# ETH_PHY_SW_L2L3.net
KiCad netlist of a schematic drawn in Altium Designer
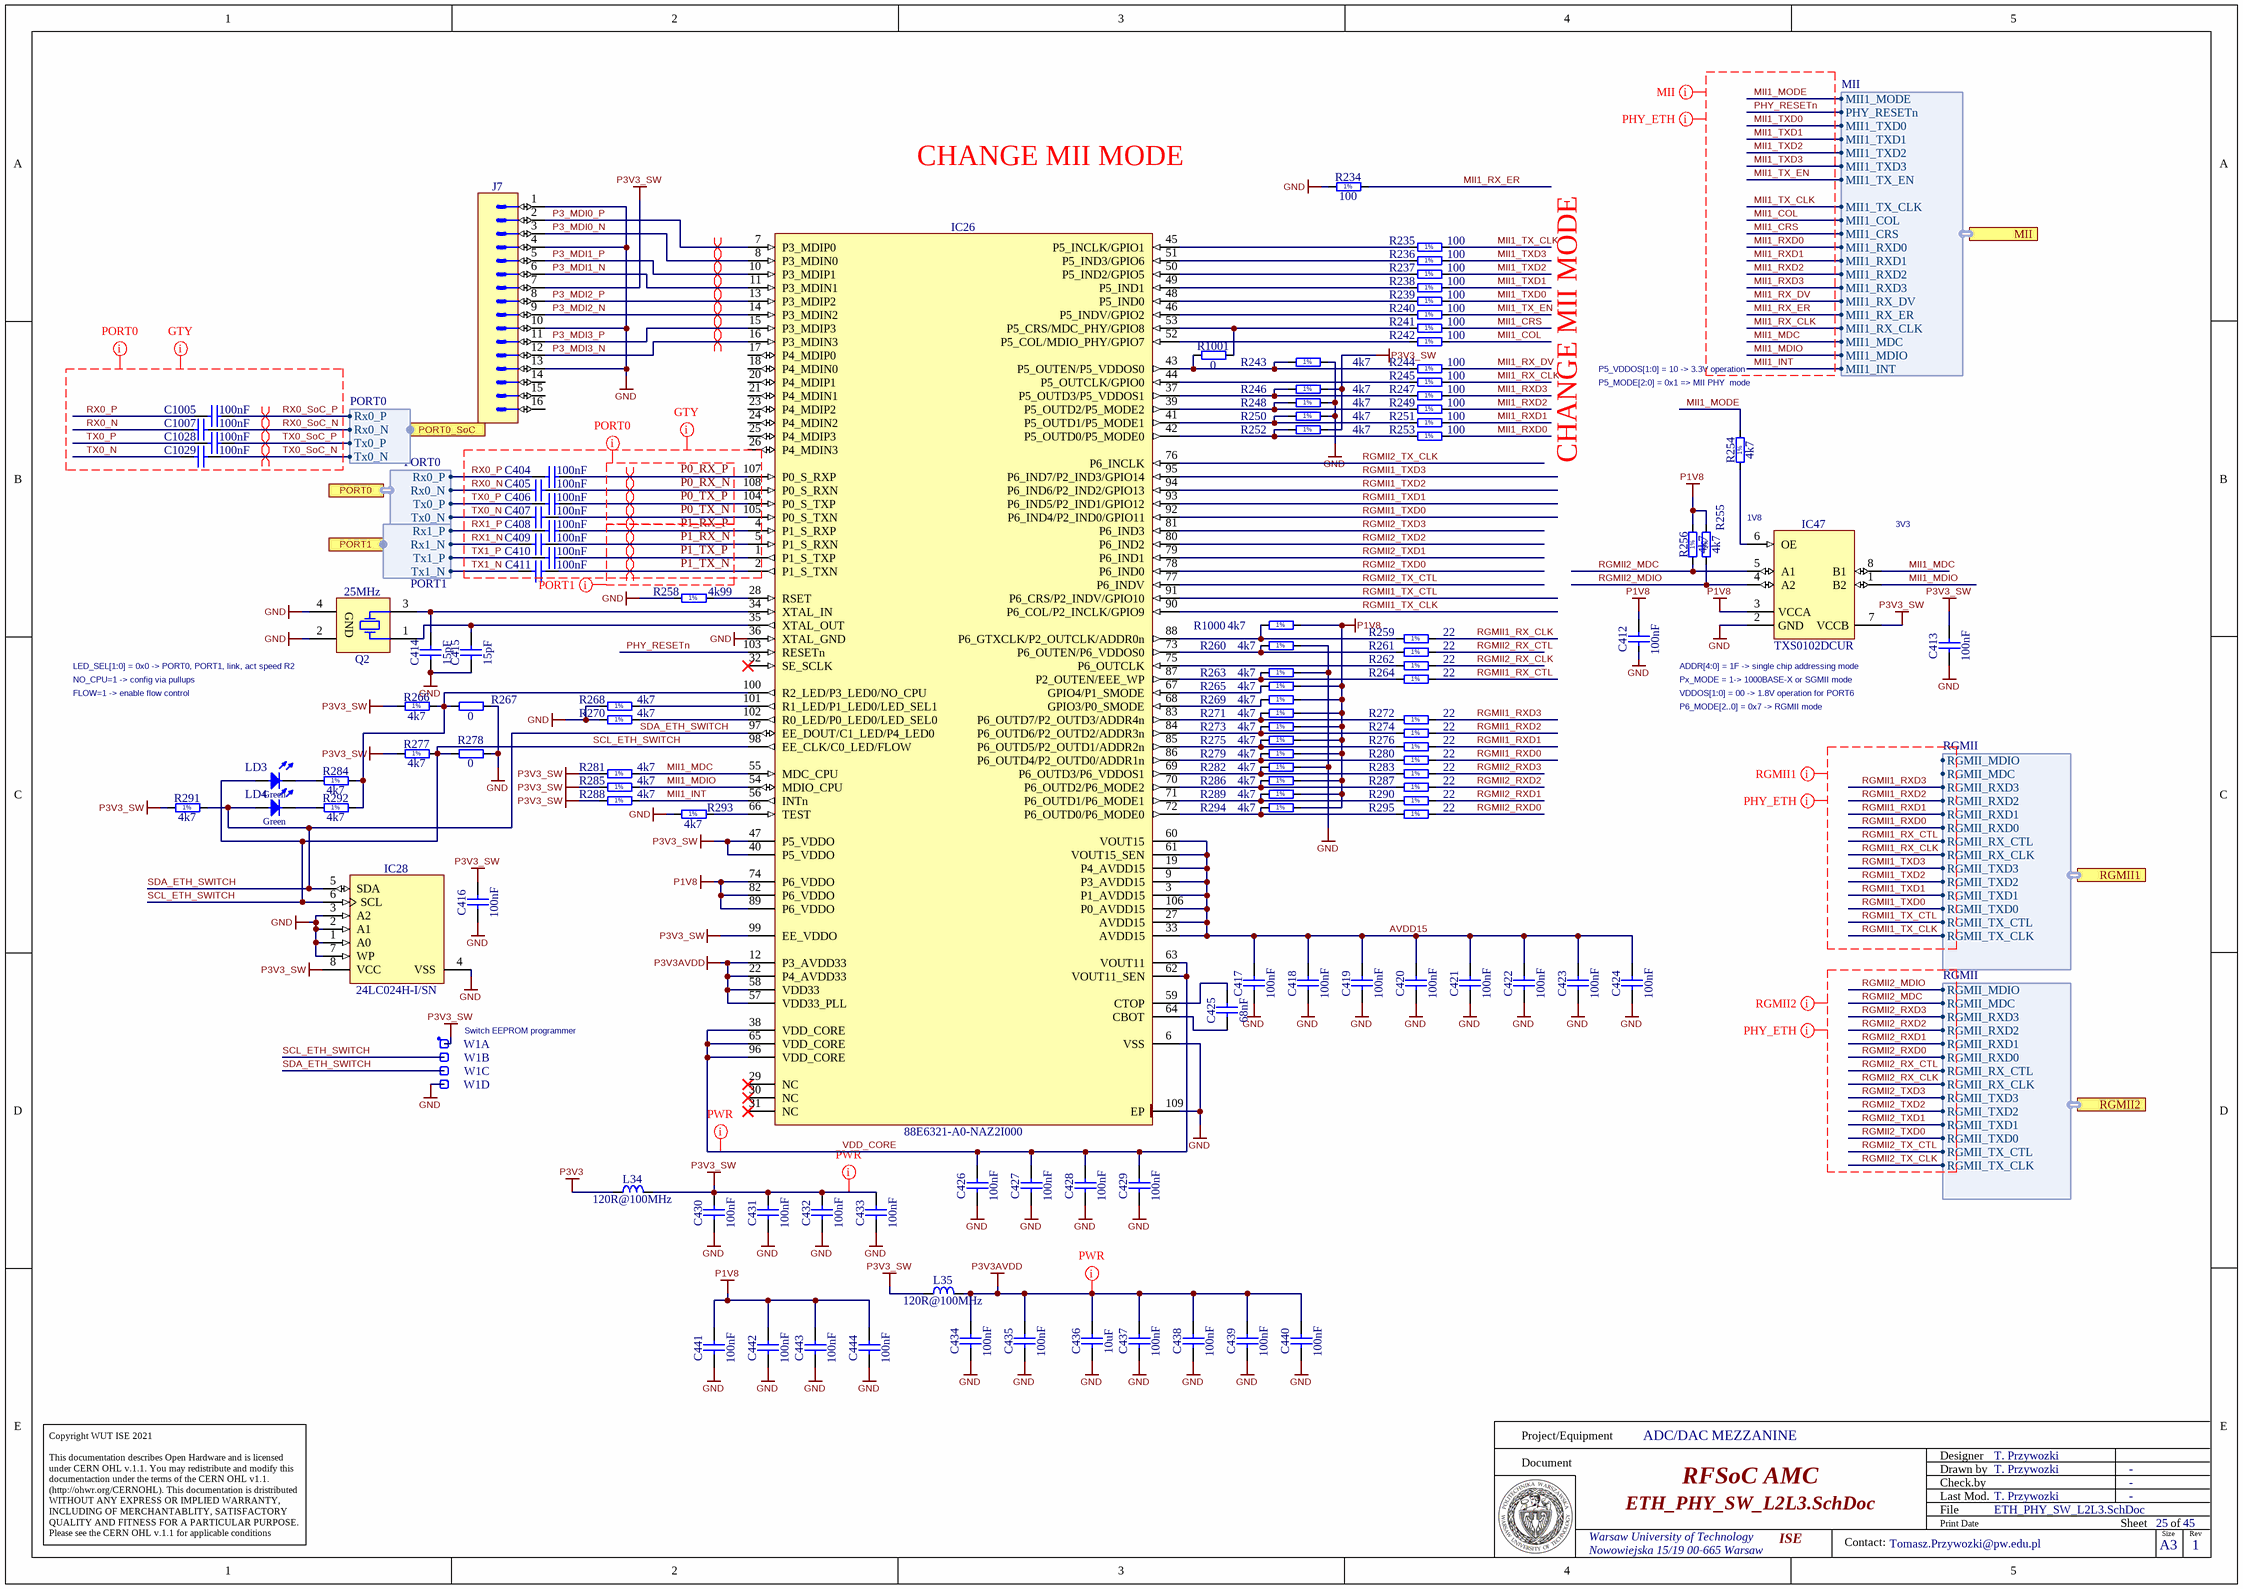
[diagram p0: ETH_PHY_SW_L2L3.SchDoc]

(export (version "E")
  (design (tool "Eeschema 10.0.6"))
  (components
    (comp (ref "C404")
      (value "100nF")
      (footprint "CAPC0603X33N")
      (description "Non-polarised capacitor")
      (fields
        (field (name "MANUFACTURER PART NUMBER") "CC0201_100NF_6.3V_10%_X5R")
        (field (name "MANUFACTURER") "GENERIC")
        (field (name "AUTHOR") "CERN DEM JLC")
      )
      (libsource (lib "Capacitors") (part "Capacitor - non polarized"))
    )
    (comp (ref "C405")
      (value "100nF")
      (footprint "CAPC0603X33N")
      (description "Non-polarised capacitor")
      (fields
        (field (name "MANUFACTURER PART NUMBER") "CC0201_100NF_6.3V_10%_X5R")
        (field (name "MANUFACTURER") "GENERIC")
        (field (name "AUTHOR") "CERN DEM JLC")
      )
      (libsource (lib "Capacitors") (part "Capacitor - non polarized"))
    )
    (comp (ref "C406")
      (value "100nF")
      (footprint "CAPC0603X33N")
      (description "Non-polarised capacitor")
      (fields
        (field (name "MANUFACTURER PART NUMBER") "CC0201_100NF_6.3V_10%_X5R")
        (field (name "MANUFACTURER") "GENERIC")
        (field (name "AUTHOR") "CERN DEM JLC")
      )
      (libsource (lib "Capacitors") (part "Capacitor - non polarized"))
    )
    (comp (ref "C407")
      (value "100nF")
      (footprint "CAPC0603X33N")
      (description "Non-polarised capacitor")
      (fields
        (field (name "MANUFACTURER PART NUMBER") "CC0201_100NF_6.3V_10%_X5R")
        (field (name "MANUFACTURER") "GENERIC")
        (field (name "AUTHOR") "CERN DEM JLC")
      )
      (libsource (lib "Capacitors") (part "Capacitor - non polarized"))
    )
    (comp (ref "C408")
      (value "100nF")
      (footprint "CAPC0603X33N")
      (description "Non-polarised capacitor")
      (fields
        (field (name "MANUFACTURER PART NUMBER") "CC0201_100NF_6.3V_10%_X5R")
        (field (name "MANUFACTURER") "GENERIC")
        (field (name "AUTHOR") "CERN DEM JLC")
      )
      (libsource (lib "Capacitors") (part "Capacitor - non polarized"))
    )
    (comp (ref "C409")
      (value "100nF")
      (footprint "CAPC0603X33N")
      (description "Non-polarised capacitor")
      (fields
        (field (name "MANUFACTURER PART NUMBER") "CC0201_100NF_6.3V_10%_X5R")
        (field (name "MANUFACTURER") "GENERIC")
        (field (name "AUTHOR") "CERN DEM JLC")
      )
      (libsource (lib "Capacitors") (part "Capacitor - non polarized"))
    )
    (comp (ref "C410")
      (value "100nF")
      (footprint "CAPC0603X33N")
      (description "Non-polarised capacitor")
      (fields
        (field (name "MANUFACTURER PART NUMBER") "CC0201_100NF_6.3V_10%_X5R")
        (field (name "MANUFACTURER") "GENERIC")
        (field (name "AUTHOR") "CERN DEM JLC")
      )
      (libsource (lib "Capacitors") (part "Capacitor - non polarized"))
    )
    (comp (ref "C411")
      (value "100nF")
      (footprint "CAPC0603X33N")
      (description "Non-polarised capacitor")
      (fields
        (field (name "MANUFACTURER PART NUMBER") "CC0201_100NF_6.3V_10%_X5R")
        (field (name "MANUFACTURER") "GENERIC")
        (field (name "AUTHOR") "CERN DEM JLC")
      )
      (libsource (lib "Capacitors") (part "Capacitor - non polarized"))
    )
    (comp (ref "C412")
      (value "100nF")
      (footprint "CAPC0603X33N")
      (description "Non-polarised capacitor")
      (fields
        (field (name "MANUFACTURER PART NUMBER") "CC0201_100NF_6.3V_10%_X5R")
        (field (name "MANUFACTURER") "GENERIC")
        (field (name "AUTHOR") "CERN DEM JLC")
      )
      (libsource (lib "Capacitors") (part "Capacitor - non polarized"))
    )
    (comp (ref "C413")
      (value "100nF")
      (footprint "CAPC0603X33N")
      (description "Non-polarised capacitor")
      (fields
        (field (name "MANUFACTURER PART NUMBER") "CC0201_100NF_6.3V_10%_X5R")
        (field (name "MANUFACTURER") "GENERIC")
        (field (name "AUTHOR") "CERN DEM JLC")
      )
      (libsource (lib "Capacitors") (part "Capacitor - non polarized"))
    )
    (comp (ref "C414")
      (value "15pF")
      (footprint "CAPC1005X55N")
      (description "Non-polarised capacitor")
      (fields
        (field (name "MANUFACTURER PART NUMBER") "CC0402_15PF_50V_5%_C0G")
        (field (name "MANUFACTURER") "GENERIC")
        (field (name "AUTHOR") "CERN DEM JLC")
      )
      (libsource (lib "Capacitors") (part "Capacitor - non polarized"))
    )
    (comp (ref "C415")
      (value "15pF")
      (footprint "CAPC1005X55N")
      (description "Non-polarised capacitor")
      (fields
        (field (name "MANUFACTURER PART NUMBER") "CC0402_15PF_50V_5%_C0G")
        (field (name "MANUFACTURER") "GENERIC")
        (field (name "AUTHOR") "CERN DEM JLC")
      )
      (libsource (lib "Capacitors") (part "Capacitor - non polarized"))
    )
    (comp (ref "C416")
      (value "100nF")
      (footprint "CAPC0603X33N")
      (description "Non-polarised capacitor")
      (fields
        (field (name "MANUFACTURER PART NUMBER") "CC0201_100NF_6.3V_10%_X5R")
        (field (name "MANUFACTURER") "GENERIC")
        (field (name "AUTHOR") "CERN DEM JLC")
      )
      (libsource (lib "Capacitors") (part "Capacitor - non polarized"))
    )
    (comp (ref "C417")
      (value "100nF")
      (footprint "CAPC0603X33N")
      (description "Non-polarised capacitor")
      (fields
        (field (name "MANUFACTURER PART NUMBER") "CC0201_100NF_6.3V_10%_X5R")
        (field (name "MANUFACTURER") "GENERIC")
        (field (name "AUTHOR") "CERN DEM JLC")
      )
      (libsource (lib "Capacitors") (part "Capacitor - non polarized"))
    )
    (comp (ref "C418")
      (value "100nF")
      (footprint "CAPC0603X33N")
      (description "Non-polarised capacitor")
      (fields
        (field (name "MANUFACTURER PART NUMBER") "CC0201_100NF_6.3V_10%_X5R")
        (field (name "MANUFACTURER") "GENERIC")
        (field (name "AUTHOR") "CERN DEM JLC")
      )
      (libsource (lib "Capacitors") (part "Capacitor - non polarized"))
    )
    (comp (ref "C419")
      (value "100nF")
      (footprint "CAPC0603X33N")
      (description "Non-polarised capacitor")
      (fields
        (field (name "MANUFACTURER PART NUMBER") "CC0201_100NF_6.3V_10%_X5R")
        (field (name "MANUFACTURER") "GENERIC")
        (field (name "AUTHOR") "CERN DEM JLC")
      )
      (libsource (lib "Capacitors") (part "Capacitor - non polarized"))
    )
    (comp (ref "C420")
      (value "100nF")
      (footprint "CAPC0603X33N")
      (description "Non-polarised capacitor")
      (fields
        (field (name "MANUFACTURER PART NUMBER") "CC0201_100NF_6.3V_10%_X5R")
        (field (name "MANUFACTURER") "GENERIC")
        (field (name "AUTHOR") "CERN DEM JLC")
      )
      (libsource (lib "Capacitors") (part "Capacitor - non polarized"))
    )
    (comp (ref "C421")
      (value "100nF")
      (footprint "CAPC0603X33N")
      (description "Non-polarised capacitor")
      (fields
        (field (name "MANUFACTURER PART NUMBER") "CC0201_100NF_6.3V_10%_X5R")
        (field (name "MANUFACTURER") "GENERIC")
        (field (name "AUTHOR") "CERN DEM JLC")
      )
      (libsource (lib "Capacitors") (part "Capacitor - non polarized"))
    )
    (comp (ref "C422")
      (value "100nF")
      (footprint "CAPC0603X33N")
      (description "Non-polarised capacitor")
      (fields
        (field (name "MANUFACTURER PART NUMBER") "CC0201_100NF_6.3V_10%_X5R")
        (field (name "MANUFACTURER") "GENERIC")
        (field (name "AUTHOR") "CERN DEM JLC")
      )
      (libsource (lib "Capacitors") (part "Capacitor - non polarized"))
    )
    (comp (ref "C423")
      (value "100nF")
      (footprint "CAPC0603X33N")
      (description "Non-polarised capacitor")
      (fields
        (field (name "MANUFACTURER PART NUMBER") "CC0201_100NF_6.3V_10%_X5R")
        (field (name "MANUFACTURER") "GENERIC")
        (field (name "AUTHOR") "CERN DEM JLC")
      )
      (libsource (lib "Capacitors") (part "Capacitor - non polarized"))
    )
    (comp (ref "C424")
      (value "100nF")
      (footprint "CAPC0603X33N")
      (description "Non-polarised capacitor")
      (fields
        (field (name "MANUFACTURER PART NUMBER") "CC0201_100NF_6.3V_10%_X5R")
        (field (name "MANUFACTURER") "GENERIC")
        (field (name "AUTHOR") "CERN DEM JLC")
      )
      (libsource (lib "Capacitors") (part "Capacitor - non polarized"))
    )
    (comp (ref "C425")
      (value "68nF")
      (footprint "CAPC1005X55N")
      (description "Non-polarised capacitor")
      (fields
        (field (name "MANUFACTURER PART NUMBER") "CC0402_68NF_16V_10%_X7R")
        (field (name "MANUFACTURER") "GENERIC")
        (field (name "AUTHOR") "CERN DEM JLC")
      )
      (libsource (lib "Capacitors") (part "Capacitor - non polarized"))
    )
    (comp (ref "C426")
      (value "100nF")
      (footprint "CAPC0603X33N")
      (description "Non-polarised capacitor")
      (fields
        (field (name "MANUFACTURER PART NUMBER") "CC0201_100NF_6.3V_10%_X5R")
        (field (name "MANUFACTURER") "GENERIC")
        (field (name "AUTHOR") "CERN DEM JLC")
      )
      (libsource (lib "Capacitors") (part "Capacitor - non polarized"))
    )
    (comp (ref "C427")
      (value "100nF")
      (footprint "CAPC0603X33N")
      (description "Non-polarised capacitor")
      (fields
        (field (name "MANUFACTURER PART NUMBER") "CC0201_100NF_6.3V_10%_X5R")
        (field (name "MANUFACTURER") "GENERIC")
        (field (name "AUTHOR") "CERN DEM JLC")
      )
      (libsource (lib "Capacitors") (part "Capacitor - non polarized"))
    )
    (comp (ref "C428")
      (value "100nF")
      (footprint "CAPC0603X33N")
      (description "Non-polarised capacitor")
      (fields
        (field (name "MANUFACTURER PART NUMBER") "CC0201_100NF_6.3V_10%_X5R")
        (field (name "MANUFACTURER") "GENERIC")
        (field (name "AUTHOR") "CERN DEM JLC")
      )
      (libsource (lib "Capacitors") (part "Capacitor - non polarized"))
    )
    (comp (ref "C429")
      (value "100nF")
      (footprint "CAPC0603X33N")
      (description "Non-polarised capacitor")
      (fields
        (field (name "MANUFACTURER PART NUMBER") "CC0201_100NF_6.3V_10%_X5R")
        (field (name "MANUFACTURER") "GENERIC")
        (field (name "AUTHOR") "CERN DEM JLC")
      )
      (libsource (lib "Capacitors") (part "Capacitor - non polarized"))
    )
    (comp (ref "C430")
      (value "100nF")
      (footprint "CAPC0603X33N")
      (description "Non-polarised capacitor")
      (fields
        (field (name "MANUFACTURER PART NUMBER") "CC0201_100NF_6.3V_10%_X5R")
        (field (name "MANUFACTURER") "GENERIC")
        (field (name "AUTHOR") "CERN DEM JLC")
      )
      (libsource (lib "Capacitors") (part "Capacitor - non polarized"))
    )
    (comp (ref "C431")
      (value "100nF")
      (footprint "CAPC0603X33N")
      (description "Non-polarised capacitor")
      (fields
        (field (name "MANUFACTURER PART NUMBER") "CC0201_100NF_6.3V_10%_X5R")
        (field (name "MANUFACTURER") "GENERIC")
        (field (name "AUTHOR") "CERN DEM JLC")
      )
      (libsource (lib "Capacitors") (part "Capacitor - non polarized"))
    )
    (comp (ref "C432")
      (value "100nF")
      (footprint "CAPC0603X33N")
      (description "Non-polarised capacitor")
      (fields
        (field (name "MANUFACTURER PART NUMBER") "CC0201_100NF_6.3V_10%_X5R")
        (field (name "MANUFACTURER") "GENERIC")
        (field (name "AUTHOR") "CERN DEM JLC")
      )
      (libsource (lib "Capacitors") (part "Capacitor - non polarized"))
    )
    (comp (ref "C433")
      (value "100nF")
      (footprint "CAPC0603X33N")
      (description "Non-polarised capacitor")
      (fields
        (field (name "MANUFACTURER PART NUMBER") "CC0201_100NF_6.3V_10%_X5R")
        (field (name "MANUFACTURER") "GENERIC")
        (field (name "AUTHOR") "CERN DEM JLC")
      )
      (libsource (lib "Capacitors") (part "Capacitor - non polarized"))
    )
    (comp (ref "C434")
      (value "100nF")
      (footprint "CAPC0603X33N")
      (description "Non-polarised capacitor")
      (fields
        (field (name "MANUFACTURER PART NUMBER") "CC0201_100NF_6.3V_10%_X5R")
        (field (name "MANUFACTURER") "GENERIC")
        (field (name "AUTHOR") "CERN DEM JLC")
      )
      (libsource (lib "Capacitors") (part "Capacitor - non polarized"))
    )
    (comp (ref "C435")
      (value "100nF")
      (footprint "CAPC0603X33N")
      (description "Non-polarised capacitor")
      (fields
        (field (name "MANUFACTURER PART NUMBER") "CC0201_100NF_6.3V_10%_X5R")
        (field (name "MANUFACTURER") "GENERIC")
        (field (name "AUTHOR") "CERN DEM JLC")
      )
      (libsource (lib "Capacitors") (part "Capacitor - non polarized"))
    )
    (comp (ref "C436")
      (value "10uF")
      (footprint "CAPC1608X87N")
      (description "Non-polarised capacitor")
      (fields
        (field (name "MANUFACTURER PART NUMBER") "CC0603_10uF_6.3V_20%_X5R")
        (field (name "MANUFACTURER") "GENERIC")
        (field (name "AUTHOR") "CERN DEM JLC")
      )
      (libsource (lib "Capacitors") (part "Capacitor - non polarized"))
    )
    (comp (ref "C437")
      (value "100nF")
      (footprint "CAPC0603X33N")
      (description "Non-polarised capacitor")
      (fields
        (field (name "MANUFACTURER PART NUMBER") "CC0201_100NF_6.3V_10%_X5R")
        (field (name "MANUFACTURER") "GENERIC")
        (field (name "AUTHOR") "CERN DEM JLC")
      )
      (libsource (lib "Capacitors") (part "Capacitor - non polarized"))
    )
    (comp (ref "C438")
      (value "100nF")
      (footprint "CAPC0603X33N")
      (description "Non-polarised capacitor")
      (fields
        (field (name "MANUFACTURER PART NUMBER") "CC0201_100NF_6.3V_10%_X5R")
        (field (name "MANUFACTURER") "GENERIC")
        (field (name "AUTHOR") "CERN DEM JLC")
      )
      (libsource (lib "Capacitors") (part "Capacitor - non polarized"))
    )
    (comp (ref "C439")
      (value "100nF")
      (footprint "CAPC0603X33N")
      (description "Non-polarised capacitor")
      (fields
        (field (name "MANUFACTURER PART NUMBER") "CC0201_100NF_6.3V_10%_X5R")
        (field (name "MANUFACTURER") "GENERIC")
        (field (name "AUTHOR") "CERN DEM JLC")
      )
      (libsource (lib "Capacitors") (part "Capacitor - non polarized"))
    )
    (comp (ref "C440")
      (value "100nF")
      (footprint "CAPC0603X33N")
      (description "Non-polarised capacitor")
      (fields
        (field (name "MANUFACTURER PART NUMBER") "CC0201_100NF_6.3V_10%_X5R")
        (field (name "MANUFACTURER") "GENERIC")
        (field (name "AUTHOR") "CERN DEM JLC")
      )
      (libsource (lib "Capacitors") (part "Capacitor - non polarized"))
    )
    (comp (ref "C441")
      (value "100nF")
      (footprint "CAPC0603X33N")
      (description "Non-polarised capacitor")
      (fields
        (field (name "MANUFACTURER PART NUMBER") "CC0201_100NF_6.3V_10%_X5R")
        (field (name "MANUFACTURER") "GENERIC")
        (field (name "AUTHOR") "CERN DEM JLC")
      )
      (libsource (lib "Capacitors") (part "Capacitor - non polarized"))
    )
    (comp (ref "C442")
      (value "100nF")
      (footprint "CAPC0603X33N")
      (description "Non-polarised capacitor")
      (fields
        (field (name "MANUFACTURER PART NUMBER") "CC0201_100NF_6.3V_10%_X5R")
        (field (name "MANUFACTURER") "GENERIC")
        (field (name "AUTHOR") "CERN DEM JLC")
      )
      (libsource (lib "Capacitors") (part "Capacitor - non polarized"))
    )
    (comp (ref "C443")
      (value "100nF")
      (footprint "CAPC0603X33N")
      (description "Non-polarised capacitor")
      (fields
        (field (name "MANUFACTURER PART NUMBER") "CC0201_100NF_6.3V_10%_X5R")
        (field (name "MANUFACTURER") "GENERIC")
        (field (name "AUTHOR") "CERN DEM JLC")
      )
      (libsource (lib "Capacitors") (part "Capacitor - non polarized"))
    )
    (comp (ref "C444")
      (value "100nF")
      (footprint "CAPC0603X33N")
      (description "Non-polarised capacitor")
      (fields
        (field (name "MANUFACTURER PART NUMBER") "CC0201_100NF_6.3V_10%_X5R")
        (field (name "MANUFACTURER") "GENERIC")
        (field (name "AUTHOR") "CERN DEM JLC")
      )
      (libsource (lib "Capacitors") (part "Capacitor - non polarized"))
    )
    (comp (ref "C1005")
      (value "100nF")
      (footprint "CAPC0603X33N")
      (description "Non-polarised capacitor")
      (fields
        (field (name "MANUFACTURER PART NUMBER") "CC0201_100NF_6.3V_10%_X5R")
        (field (name "MANUFACTURER") "GENERIC")
        (field (name "AUTHOR") "CERN DEM JLC")
      )
      (libsource (lib "Capacitors") (part "Capacitor - non polarized"))
    )
    (comp (ref "C1007")
      (value "100nF")
      (footprint "CAPC0603X33N")
      (description "Non-polarised capacitor")
      (fields
        (field (name "MANUFACTURER PART NUMBER") "CC0201_100NF_6.3V_10%_X5R")
        (field (name "MANUFACTURER") "GENERIC")
        (field (name "AUTHOR") "CERN DEM JLC")
      )
      (libsource (lib "Capacitors") (part "Capacitor - non polarized"))
    )
    (comp (ref "C1028")
      (value "100nF")
      (footprint "CAPC0603X33N")
      (description "Non-polarised capacitor")
      (fields
        (field (name "MANUFACTURER PART NUMBER") "CC0201_100NF_6.3V_10%_X5R")
        (field (name "MANUFACTURER") "GENERIC")
        (field (name "AUTHOR") "CERN DEM JLC")
      )
      (libsource (lib "Capacitors") (part "Capacitor - non polarized"))
    )
    (comp (ref "C1029")
      (value "100nF")
      (footprint "CAPC0603X33N")
      (description "Non-polarised capacitor")
      (fields
        (field (name "MANUFACTURER PART NUMBER") "CC0201_100NF_6.3V_10%_X5R")
        (field (name "MANUFACTURER") "GENERIC")
        (field (name "AUTHOR") "CERN DEM JLC")
      )
      (libsource (lib "Capacitors") (part "Capacitor - non polarized"))
    )
    (comp (ref "IC26")
      (value "88E6321-A0-NAZ2I000")
      (footprint "QFN40P1200X1200X90-109N-S475")
      (description "7 Port Gigabit AVB Switch With 2 PHYs And Energy Efficient Ethernet (EEE)")
      (fields (field (name "MANUFACTURER") "MARVELL") (field (name "AUTHOR") "CERN DEM MR"))
      (libsource (lib "ICs And Semiconductors") (part "88E6321-A0-NAZ"))
    )
    (comp (ref "IC28")
      (value "24LC024H-I/SN")
      (footprint "SOIC127P600X175-8N")
      (description "2K I2C Serial EEPROM With Half-Array Write Protect")
      (fields (field (name "MANUFACTURER") "MICROCHIP TECHNOLOGY") (field (name "AUTHOR") "CERN DEM JLC"))
      (libsource (lib "ICs And Semiconductors") (part "24LC024H-I/SN"))
    )
    (comp (ref "IC47")
      (value "TXS0102DCUR")
      (footprint "SOP50P310X90-8N")
      (description "2-Bit Bidirectionnal Voltage-Level Translator for Open-Drain And Push-Pull Applications")
      (fields (field (name "MANUFACTURER") "TEXAS INSTRUMENTS") (field (name "AUTHOR") "CERN DEM JLC"))
      (libsource (lib "ICs And Semiconductors") (part "TXS0102DCU"))
    )
    (comp (ref "J7")
      (value "Milli-Grid™")
      (footprint "MOLEX_87759-1650")
      (description "Connector 16 Male")
      (fields
        (field (name "PART NUMBER") "MOLEX_87759-1650")
        (field (name "MANUFACTURER") "MOLEX")
        (field (name "AUTHOR") "CERN DEM MR")
      )
      (libsource (lib "Connectors") (part "Connector 16 Male"))
    )
    (comp (ref "L34")
      (value "120R@100MHz")
      (footprint "INDC1608X65N")
      (description "Inductor")
      (fields
        (field (name "MANUFACTURER PART NUMBER") "BLM18SG121TN1D")
        (field (name "MANUFACTURER") "MURATA")
        (field (name "AUTHOR") "CERN DEM JLC")
      )
      (libsource (lib "Inductors & Transformers") (part "Inductor"))
    )
    (comp (ref "L35")
      (value "120R@100MHz")
      (footprint "INDC1608X65N")
      (description "Inductor")
      (fields
        (field (name "MANUFACTURER PART NUMBER") "BLM18SG121TN1D")
        (field (name "MANUFACTURER") "MURATA")
        (field (name "AUTHOR") "CERN DEM JLC")
      )
      (libsource (lib "Inductors & Transformers") (part "Inductor"))
    )
    (comp (ref "LD3")
      (value "Green")
      (footprint "LED_KINGBRIGHT_KPH-1608CGCK")
      (description "LED Green 1C 2A")
      (fields
        (field (name "MANUFACTURER PART NUMBER") "KPH-1608CGCK")
        (field (name "MANUFACTURER") "KINGBRIGHT")
        (field (name "AUTHOR") "CERN DEM JLC")
      )
      (libsource (lib "ICs And Semiconductors") (part "LED Green 1C 2A"))
    )
    (comp (ref "LD4")
      (value "Green")
      (footprint "LED_KINGBRIGHT_KPH-1608CGCK")
      (description "LED Green 1C 2A")
      (fields
        (field (name "MANUFACTURER PART NUMBER") "KPH-1608CGCK")
        (field (name "MANUFACTURER") "KINGBRIGHT")
        (field (name "AUTHOR") "CERN DEM JLC")
      )
      (libsource (lib "ICs And Semiconductors") (part "LED Green 1C 2A"))
    )
    (comp (ref "Q2")
      (value "25MHz")
      (footprint "XTAL_TXC_8Y")
      (description "Crystal 4 pins 1=XTAL Control 2=GND3=XTAL 4=GND")
      (fields
        (field (name "MANUFACTURER PART NUMBER") "8Y-25.000MAAJ-T")
        (field (name "MANUFACTURER") "TXC CORPORATION")
        (field (name "AUTHOR") "CERN DEM JLC")
      )
      (libsource (lib "ICs And Semiconductors") (part "Quartz Crystal 1X 2GND 3X 4GND"))
    )
    (comp (ref "R234")
      (value "100")
      (footprint "RESC0603X28N")
      (description "Resistor - 1%")
      (fields
        (field (name "MANUFACTURER PART NUMBER") "R0201_100R_1%_0.05W_200PPM")
        (field (name "MANUFACTURER") "GENERIC")
        (field (name "AUTHOR") "CERN DEM JLC")
      )
      (libsource (lib "Resistors") (part "Resistor - 1%"))
    )
    (comp (ref "R235")
      (value "100")
      (footprint "RESC0603X28N")
      (description "Resistor - 1%")
      (fields
        (field (name "MANUFACTURER PART NUMBER") "R0201_100R_1%_0.05W_200PPM")
        (field (name "MANUFACTURER") "GENERIC")
        (field (name "AUTHOR") "CERN DEM JLC")
      )
      (libsource (lib "Resistors") (part "Resistor - 1%"))
    )
    (comp (ref "R236")
      (value "100")
      (footprint "RESC0603X28N")
      (description "Resistor - 1%")
      (fields
        (field (name "MANUFACTURER PART NUMBER") "R0201_100R_1%_0.05W_200PPM")
        (field (name "MANUFACTURER") "GENERIC")
        (field (name "AUTHOR") "CERN DEM JLC")
      )
      (libsource (lib "Resistors") (part "Resistor - 1%"))
    )
    (comp (ref "R237")
      (value "100")
      (footprint "RESC0603X28N")
      (description "Resistor - 1%")
      (fields
        (field (name "MANUFACTURER PART NUMBER") "R0201_100R_1%_0.05W_200PPM")
        (field (name "MANUFACTURER") "GENERIC")
        (field (name "AUTHOR") "CERN DEM JLC")
      )
      (libsource (lib "Resistors") (part "Resistor - 1%"))
    )
    (comp (ref "R238")
      (value "100")
      (footprint "RESC0603X28N")
      (description "Resistor - 1%")
      (fields
        (field (name "MANUFACTURER PART NUMBER") "R0201_100R_1%_0.05W_200PPM")
        (field (name "MANUFACTURER") "GENERIC")
        (field (name "AUTHOR") "CERN DEM JLC")
      )
      (libsource (lib "Resistors") (part "Resistor - 1%"))
    )
    (comp (ref "R239")
      (value "100")
      (footprint "RESC0603X28N")
      (description "Resistor - 1%")
      (fields
        (field (name "MANUFACTURER PART NUMBER") "R0201_100R_1%_0.05W_200PPM")
        (field (name "MANUFACTURER") "GENERIC")
        (field (name "AUTHOR") "CERN DEM JLC")
      )
      (libsource (lib "Resistors") (part "Resistor - 1%"))
    )
    (comp (ref "R240")
      (value "100")
      (footprint "RESC0603X28N")
      (description "Resistor - 1%")
      (fields
        (field (name "MANUFACTURER PART NUMBER") "R0201_100R_1%_0.05W_200PPM")
        (field (name "MANUFACTURER") "GENERIC")
        (field (name "AUTHOR") "CERN DEM JLC")
      )
      (libsource (lib "Resistors") (part "Resistor - 1%"))
    )
    (comp (ref "R241")
      (value "100")
      (footprint "RESC0603X28N")
      (description "Resistor - 1%")
      (fields
        (field (name "MANUFACTURER PART NUMBER") "R0201_100R_1%_0.05W_200PPM")
        (field (name "MANUFACTURER") "GENERIC")
        (field (name "AUTHOR") "CERN DEM JLC")
      )
      (libsource (lib "Resistors") (part "Resistor - 1%"))
    )
    (comp (ref "R242")
      (value "100")
      (footprint "RESC0603X28N")
      (description "Resistor - 1%")
      (fields
        (field (name "MANUFACTURER PART NUMBER") "R0201_100R_1%_0.05W_200PPM")
        (field (name "MANUFACTURER") "GENERIC")
        (field (name "AUTHOR") "CERN DEM JLC")
      )
      (libsource (lib "Resistors") (part "Resistor - 1%"))
    )
    (comp (ref "R243")
      (value "4k7")
      (footprint "RESC1005X40N")
      (description "Resistor - 1%")
      (fields
        (field (name "MANUFACTURER PART NUMBER") "R0402_4K7_1%_0.0625W_100PPM")
        (field (name "MANUFACTURER") "GENERIC")
        (field (name "AUTHOR") "CERN DEM JLC")
      )
      (libsource (lib "Resistors") (part "Resistor - 1%"))
    )
    (comp (ref "R244")
      (value "100")
      (footprint "RESC0603X28N")
      (description "Resistor - 1%")
      (fields
        (field (name "MANUFACTURER PART NUMBER") "R0201_100R_1%_0.05W_200PPM")
        (field (name "MANUFACTURER") "GENERIC")
        (field (name "AUTHOR") "CERN DEM JLC")
      )
      (libsource (lib "Resistors") (part "Resistor - 1%"))
    )
    (comp (ref "R245")
      (value "100")
      (footprint "RESC0603X28N")
      (description "Resistor - 1%")
      (fields
        (field (name "MANUFACTURER PART NUMBER") "R0201_100R_1%_0.05W_200PPM")
        (field (name "MANUFACTURER") "GENERIC")
        (field (name "AUTHOR") "CERN DEM JLC")
      )
      (libsource (lib "Resistors") (part "Resistor - 1%"))
    )
    (comp (ref "R246")
      (value "4k7")
      (footprint "RESC1005X40N")
      (description "Resistor - 1%")
      (fields
        (field (name "MANUFACTURER PART NUMBER") "R0402_4K7_1%_0.0625W_100PPM")
        (field (name "MANUFACTURER") "GENERIC")
        (field (name "AUTHOR") "CERN DEM JLC")
      )
      (libsource (lib "Resistors") (part "Resistor - 1%"))
    )
    (comp (ref "R247")
      (value "100")
      (footprint "RESC0603X28N")
      (description "Resistor - 1%")
      (fields
        (field (name "MANUFACTURER PART NUMBER") "R0201_100R_1%_0.05W_200PPM")
        (field (name "MANUFACTURER") "GENERIC")
        (field (name "AUTHOR") "CERN DEM JLC")
      )
      (libsource (lib "Resistors") (part "Resistor - 1%"))
    )
    (comp (ref "R248")
      (value "4k7")
      (footprint "RESC1005X40N")
      (description "Resistor - 1%")
      (fields
        (field (name "MANUFACTURER PART NUMBER") "R0402_4K7_1%_0.0625W_100PPM")
        (field (name "MANUFACTURER") "GENERIC")
        (field (name "AUTHOR") "CERN DEM JLC")
      )
      (libsource (lib "Resistors") (part "Resistor - 1%"))
    )
    (comp (ref "R249")
      (value "100")
      (footprint "RESC0603X28N")
      (description "Resistor - 1%")
      (fields
        (field (name "MANUFACTURER PART NUMBER") "R0201_100R_1%_0.05W_200PPM")
        (field (name "MANUFACTURER") "GENERIC")
        (field (name "AUTHOR") "CERN DEM JLC")
      )
      (libsource (lib "Resistors") (part "Resistor - 1%"))
    )
    (comp (ref "R250")
      (value "4k7")
      (footprint "RESC1005X40N")
      (description "Resistor - 1%")
      (fields
        (field (name "MANUFACTURER PART NUMBER") "R0402_4K7_1%_0.0625W_100PPM")
        (field (name "MANUFACTURER") "GENERIC")
        (field (name "AUTHOR") "CERN DEM JLC")
      )
      (libsource (lib "Resistors") (part "Resistor - 1%"))
    )
    (comp (ref "R251")
      (value "100")
      (footprint "RESC0603X28N")
      (description "Resistor - 1%")
      (fields
        (field (name "MANUFACTURER PART NUMBER") "R0201_100R_1%_0.05W_200PPM")
        (field (name "MANUFACTURER") "GENERIC")
        (field (name "AUTHOR") "CERN DEM JLC")
      )
      (libsource (lib "Resistors") (part "Resistor - 1%"))
    )
    (comp (ref "R252")
      (value "4k7")
      (footprint "RESC1005X40N")
      (description "Resistor - 1%")
      (fields
        (field (name "MANUFACTURER PART NUMBER") "R0402_4K7_1%_0.0625W_100PPM")
        (field (name "MANUFACTURER") "GENERIC")
        (field (name "AUTHOR") "CERN DEM JLC")
      )
      (libsource (lib "Resistors") (part "Resistor - 1%"))
    )
    (comp (ref "R253")
      (value "100")
      (footprint "RESC0603X28N")
      (description "Resistor - 1%")
      (fields
        (field (name "MANUFACTURER PART NUMBER") "R0201_100R_1%_0.05W_200PPM")
        (field (name "MANUFACTURER") "GENERIC")
        (field (name "AUTHOR") "CERN DEM JLC")
      )
      (libsource (lib "Resistors") (part "Resistor - 1%"))
    )
    (comp (ref "R254")
      (value "4k7")
      (footprint "RESC1005X40N")
      (description "Resistor - 1%")
      (fields
        (field (name "MANUFACTURER PART NUMBER") "R0402_4K7_1%_0.0625W_100PPM")
        (field (name "MANUFACTURER") "GENERIC")
        (field (name "AUTHOR") "CERN DEM JLC")
      )
      (libsource (lib "Resistors") (part "Resistor - 1%"))
    )
    (comp (ref "R255")
      (value "4k7")
      (footprint "RESC1005X40N")
      (description "Resistor - 1%")
      (fields
        (field (name "MANUFACTURER PART NUMBER") "R0402_4K7_1%_0.0625W_100PPM")
        (field (name "MANUFACTURER") "GENERIC")
        (field (name "AUTHOR") "CERN DEM JLC")
      )
      (libsource (lib "Resistors") (part "Resistor - 1%"))
    )
    (comp (ref "R256")
      (value "4k7")
      (footprint "RESC1005X40N")
      (description "Resistor - 1%")
      (fields
        (field (name "MANUFACTURER PART NUMBER") "R0402_4K7_1%_0.0625W_100PPM")
        (field (name "MANUFACTURER") "GENERIC")
        (field (name "AUTHOR") "CERN DEM JLC")
      )
      (libsource (lib "Resistors") (part "Resistor - 1%"))
    )
    (comp (ref "R258")
      (value "4k99")
      (footprint "RESC1608X55N")
      (description "Resistor - 1%")
      (fields
        (field (name "MANUFACTURER PART NUMBER") "R0603_4K99_1%_0.063W_50PPM")
        (field (name "MANUFACTURER") "GENERIC")
        (field (name "AUTHOR") "CERN DEM JLC")
      )
      (libsource (lib "Resistors") (part "Resistor - 1%"))
    )
    (comp (ref "R259")
      (value "22")
      (footprint "RESC1005X40N")
      (description "Resistor - 1%")
      (fields
        (field (name "MANUFACTURER PART NUMBER") "R0402_22R_1%_0.0625W_100PPM")
        (field (name "MANUFACTURER") "GENERIC")
        (field (name "AUTHOR") "CERN DEM JLC")
      )
      (libsource (lib "Resistors") (part "Resistor - 1%"))
    )
    (comp (ref "R260")
      (value "4k7")
      (footprint "RESC1005X40N")
      (description "Resistor - 1%")
      (fields
        (field (name "MANUFACTURER PART NUMBER") "R0402_4K7_1%_0.0625W_100PPM")
        (field (name "MANUFACTURER") "GENERIC")
        (field (name "AUTHOR") "CERN DEM JLC")
      )
      (libsource (lib "Resistors") (part "Resistor - 1%"))
    )
    (comp (ref "R261")
      (value "22")
      (footprint "RESC1005X40N")
      (description "Resistor - 1%")
      (fields
        (field (name "MANUFACTURER PART NUMBER") "R0402_22R_1%_0.0625W_100PPM")
        (field (name "MANUFACTURER") "GENERIC")
        (field (name "AUTHOR") "CERN DEM JLC")
      )
      (libsource (lib "Resistors") (part "Resistor - 1%"))
    )
    (comp (ref "R262")
      (value "22")
      (footprint "RESC1005X40N")
      (description "Resistor - 1%")
      (fields
        (field (name "MANUFACTURER PART NUMBER") "R0402_22R_1%_0.0625W_100PPM")
        (field (name "MANUFACTURER") "GENERIC")
        (field (name "AUTHOR") "CERN DEM JLC")
      )
      (libsource (lib "Resistors") (part "Resistor - 1%"))
    )
    (comp (ref "R263")
      (value "4k7")
      (footprint "RESC1005X40N")
      (description "Resistor - 1%")
      (fields
        (field (name "MANUFACTURER PART NUMBER") "R0402_4K7_1%_0.0625W_100PPM")
        (field (name "MANUFACTURER") "GENERIC")
        (field (name "AUTHOR") "CERN DEM JLC")
      )
      (libsource (lib "Resistors") (part "Resistor - 1%"))
    )
    (comp (ref "R264")
      (value "22")
      (footprint "RESC1005X40N")
      (description "Resistor - 1%")
      (fields
        (field (name "MANUFACTURER PART NUMBER") "R0402_22R_1%_0.0625W_100PPM")
        (field (name "MANUFACTURER") "GENERIC")
        (field (name "AUTHOR") "CERN DEM JLC")
      )
      (libsource (lib "Resistors") (part "Resistor - 1%"))
    )
    (comp (ref "R265")
      (value "4k7")
      (footprint "RESC1005X40N")
      (description "Resistor - 1%")
      (fields
        (field (name "MANUFACTURER PART NUMBER") "R0402_4K7_1%_0.0625W_100PPM")
        (field (name "MANUFACTURER") "GENERIC")
        (field (name "AUTHOR") "CERN DEM JLC")
      )
      (libsource (lib "Resistors") (part "Resistor - 1%"))
    )
    (comp (ref "R266")
      (value "4k7")
      (footprint "RESC1005X40N")
      (description "Resistor - 1%")
      (fields
        (field (name "MANUFACTURER PART NUMBER") "R0402_4K7_1%_0.0625W_100PPM")
        (field (name "MANUFACTURER") "GENERIC")
        (field (name "AUTHOR") "CERN DEM JLC")
      )
      (libsource (lib "Resistors") (part "Resistor - 1%"))
    )
    (comp (ref "R267")
      (value "0")
      (footprint "RESC1005X40N")
      (description "Resistor")
      (fields
        (field (name "PART NUMBER") "R0402_0R_JUMPER")
        (field (name "MANUFACTURER") "GENERIC")
        (field (name "AUTHOR") "CERN DEM JLC")
      )
      (libsource (lib "Resistors") (part "Resistor"))
    )
    (comp (ref "R268")
      (value "4k7")
      (footprint "RESC1005X40N")
      (description "Resistor - 1%")
      (fields
        (field (name "MANUFACTURER PART NUMBER") "R0402_4K7_1%_0.0625W_100PPM")
        (field (name "MANUFACTURER") "GENERIC")
        (field (name "AUTHOR") "CERN DEM JLC")
      )
      (libsource (lib "Resistors") (part "Resistor - 1%"))
    )
    (comp (ref "R269")
      (value "4k7")
      (footprint "RESC1005X40N")
      (description "Resistor - 1%")
      (fields
        (field (name "MANUFACTURER PART NUMBER") "R0402_4K7_1%_0.0625W_100PPM")
        (field (name "MANUFACTURER") "GENERIC")
        (field (name "AUTHOR") "CERN DEM JLC")
      )
      (libsource (lib "Resistors") (part "Resistor - 1%"))
    )
    (comp (ref "R270")
      (value "4k7")
      (footprint "RESC1005X40N")
      (description "Resistor - 1%")
      (fields
        (field (name "MANUFACTURER PART NUMBER") "R0402_4K7_1%_0.0625W_100PPM")
        (field (name "MANUFACTURER") "GENERIC")
        (field (name "AUTHOR") "CERN DEM JLC")
      )
      (libsource (lib "Resistors") (part "Resistor - 1%"))
    )
    (comp (ref "R271")
      (value "4k7")
      (footprint "RESC1005X40N")
      (description "Resistor - 1%")
      (fields
        (field (name "MANUFACTURER PART NUMBER") "R0402_4K7_1%_0.0625W_100PPM")
        (field (name "MANUFACTURER") "GENERIC")
        (field (name "AUTHOR") "CERN DEM JLC")
      )
      (libsource (lib "Resistors") (part "Resistor - 1%"))
    )
    (comp (ref "R272")
      (value "22")
      (footprint "RESC1005X40N")
      (description "Resistor - 1%")
      (fields
        (field (name "MANUFACTURER PART NUMBER") "R0402_22R_1%_0.0625W_100PPM")
        (field (name "MANUFACTURER") "GENERIC")
        (field (name "AUTHOR") "CERN DEM JLC")
      )
      (libsource (lib "Resistors") (part "Resistor - 1%"))
    )
    (comp (ref "R273")
      (value "4k7")
      (footprint "RESC1005X40N")
      (description "Resistor - 1%")
      (fields
        (field (name "MANUFACTURER PART NUMBER") "R0402_4K7_1%_0.0625W_100PPM")
        (field (name "MANUFACTURER") "GENERIC")
        (field (name "AUTHOR") "CERN DEM JLC")
      )
      (libsource (lib "Resistors") (part "Resistor - 1%"))
    )
    (comp (ref "R274")
      (value "22")
      (footprint "RESC1005X40N")
      (description "Resistor - 1%")
      (fields
        (field (name "MANUFACTURER PART NUMBER") "R0402_22R_1%_0.0625W_100PPM")
        (field (name "MANUFACTURER") "GENERIC")
        (field (name "AUTHOR") "CERN DEM JLC")
      )
      (libsource (lib "Resistors") (part "Resistor - 1%"))
    )
    (comp (ref "R275")
      (value "4k7")
      (footprint "RESC1005X40N")
      (description "Resistor - 1%")
      (fields
        (field (name "MANUFACTURER PART NUMBER") "R0402_4K7_1%_0.0625W_100PPM")
        (field (name "MANUFACTURER") "GENERIC")
        (field (name "AUTHOR") "CERN DEM JLC")
      )
      (libsource (lib "Resistors") (part "Resistor - 1%"))
    )
    (comp (ref "R276")
      (value "22")
      (footprint "RESC1005X40N")
      (description "Resistor - 1%")
      (fields
        (field (name "MANUFACTURER PART NUMBER") "R0402_22R_1%_0.0625W_100PPM")
        (field (name "MANUFACTURER") "GENERIC")
        (field (name "AUTHOR") "CERN DEM JLC")
      )
      (libsource (lib "Resistors") (part "Resistor - 1%"))
    )
    (comp (ref "R277")
      (value "4k7")
      (footprint "RESC1005X40N")
      (description "Resistor - 1%")
      (fields
        (field (name "MANUFACTURER PART NUMBER") "R0402_4K7_1%_0.0625W_100PPM")
        (field (name "MANUFACTURER") "GENERIC")
        (field (name "AUTHOR") "CERN DEM JLC")
      )
      (libsource (lib "Resistors") (part "Resistor - 1%"))
    )
    (comp (ref "R278")
      (value "0")
      (footprint "RESC1005X40N")
      (description "Resistor")
      (fields
        (field (name "PART NUMBER") "R0402_0R_JUMPER")
        (field (name "MANUFACTURER") "GENERIC")
        (field (name "AUTHOR") "CERN DEM JLC")
      )
      (libsource (lib "Resistors") (part "Resistor"))
    )
    (comp (ref "R279")
      (value "4k7")
      (footprint "RESC1005X40N")
      (description "Resistor - 1%")
      (fields
        (field (name "MANUFACTURER PART NUMBER") "R0402_4K7_1%_0.0625W_100PPM")
        (field (name "MANUFACTURER") "GENERIC")
        (field (name "AUTHOR") "CERN DEM JLC")
      )
      (libsource (lib "Resistors") (part "Resistor - 1%"))
    )
    (comp (ref "R280")
      (value "22")
      (footprint "RESC1005X40N")
      (description "Resistor - 1%")
      (fields
        (field (name "MANUFACTURER PART NUMBER") "R0402_22R_1%_0.0625W_100PPM")
        (field (name "MANUFACTURER") "GENERIC")
        (field (name "AUTHOR") "CERN DEM JLC")
      )
      (libsource (lib "Resistors") (part "Resistor - 1%"))
    )
    (comp (ref "R281")
      (value "4k7")
      (footprint "RESC1005X40N")
      (description "Resistor - 1%")
      (fields
        (field (name "MANUFACTURER PART NUMBER") "R0402_4K7_1%_0.0625W_100PPM")
        (field (name "MANUFACTURER") "GENERIC")
        (field (name "AUTHOR") "CERN DEM JLC")
      )
      (libsource (lib "Resistors") (part "Resistor - 1%"))
    )
    (comp (ref "R282")
      (value "4k7")
      (footprint "RESC1005X40N")
      (description "Resistor - 1%")
      (fields
        (field (name "MANUFACTURER PART NUMBER") "R0402_4K7_1%_0.0625W_100PPM")
        (field (name "MANUFACTURER") "GENERIC")
        (field (name "AUTHOR") "CERN DEM JLC")
      )
      (libsource (lib "Resistors") (part "Resistor - 1%"))
    )
    (comp (ref "R283")
      (value "22")
      (footprint "RESC1005X40N")
      (description "Resistor - 1%")
      (fields
        (field (name "MANUFACTURER PART NUMBER") "R0402_22R_1%_0.0625W_100PPM")
        (field (name "MANUFACTURER") "GENERIC")
        (field (name "AUTHOR") "CERN DEM JLC")
      )
      (libsource (lib "Resistors") (part "Resistor - 1%"))
    )
    (comp (ref "R284")
      (value "4k7")
      (footprint "RESC1005X40N")
      (description "Resistor - 1%")
      (fields
        (field (name "MANUFACTURER PART NUMBER") "R0402_4K7_1%_0.0625W_100PPM")
        (field (name "MANUFACTURER") "GENERIC")
        (field (name "AUTHOR") "CERN DEM JLC")
      )
      (libsource (lib "Resistors") (part "Resistor - 1%"))
    )
    (comp (ref "R285")
      (value "4k7")
      (footprint "RESC1005X40N")
      (description "Resistor - 1%")
      (fields
        (field (name "MANUFACTURER PART NUMBER") "R0402_4K7_1%_0.0625W_100PPM")
        (field (name "MANUFACTURER") "GENERIC")
        (field (name "AUTHOR") "CERN DEM JLC")
      )
      (libsource (lib "Resistors") (part "Resistor - 1%"))
    )
    (comp (ref "R286")
      (value "4k7")
      (footprint "RESC1005X40N")
      (description "Resistor - 1%")
      (fields
        (field (name "MANUFACTURER PART NUMBER") "R0402_4K7_1%_0.0625W_100PPM")
        (field (name "MANUFACTURER") "GENERIC")
        (field (name "AUTHOR") "CERN DEM JLC")
      )
      (libsource (lib "Resistors") (part "Resistor - 1%"))
    )
    (comp (ref "R287")
      (value "22")
      (footprint "RESC1005X40N")
      (description "Resistor - 1%")
      (fields
        (field (name "MANUFACTURER PART NUMBER") "R0402_22R_1%_0.0625W_100PPM")
        (field (name "MANUFACTURER") "GENERIC")
        (field (name "AUTHOR") "CERN DEM JLC")
      )
      (libsource (lib "Resistors") (part "Resistor - 1%"))
    )
    (comp (ref "R288")
      (value "4k7")
      (footprint "RESC1005X40N")
      (description "Resistor - 1%")
      (fields
        (field (name "MANUFACTURER PART NUMBER") "R0402_4K7_1%_0.0625W_100PPM")
        (field (name "MANUFACTURER") "GENERIC")
        (field (name "AUTHOR") "CERN DEM JLC")
      )
      (libsource (lib "Resistors") (part "Resistor - 1%"))
    )
    (comp (ref "R289")
      (value "4k7")
      (footprint "RESC1005X40N")
      (description "Resistor - 1%")
      (fields
        (field (name "MANUFACTURER PART NUMBER") "R0402_4K7_1%_0.0625W_100PPM")
        (field (name "MANUFACTURER") "GENERIC")
        (field (name "AUTHOR") "CERN DEM JLC")
      )
      (libsource (lib "Resistors") (part "Resistor - 1%"))
    )
    (comp (ref "R290")
      (value "22")
      (footprint "RESC1005X40N")
      (description "Resistor - 1%")
      (fields
        (field (name "MANUFACTURER PART NUMBER") "R0402_22R_1%_0.0625W_100PPM")
        (field (name "MANUFACTURER") "GENERIC")
        (field (name "AUTHOR") "CERN DEM JLC")
      )
      (libsource (lib "Resistors") (part "Resistor - 1%"))
    )
    (comp (ref "R291")
      (value "4k7")
      (footprint "RESC1005X40N")
      (description "Resistor - 1%")
      (fields
        (field (name "MANUFACTURER PART NUMBER") "R0402_4K7_1%_0.0625W_100PPM")
        (field (name "MANUFACTURER") "GENERIC")
        (field (name "AUTHOR") "CERN DEM JLC")
      )
      (libsource (lib "Resistors") (part "Resistor - 1%"))
    )
    (comp (ref "R292")
      (value "4k7")
      (footprint "RESC1005X40N")
      (description "Resistor - 1%")
      (fields
        (field (name "MANUFACTURER PART NUMBER") "R0402_4K7_1%_0.0625W_100PPM")
        (field (name "MANUFACTURER") "GENERIC")
        (field (name "AUTHOR") "CERN DEM JLC")
      )
      (libsource (lib "Resistors") (part "Resistor - 1%"))
    )
    (comp (ref "R293")
      (value "4k7")
      (footprint "RESC1005X40N")
      (description "Resistor - 1%")
      (fields
        (field (name "MANUFACTURER PART NUMBER") "R0402_4K7_1%_0.0625W_100PPM")
        (field (name "MANUFACTURER") "GENERIC")
        (field (name "AUTHOR") "CERN DEM JLC")
      )
      (libsource (lib "Resistors") (part "Resistor - 1%"))
    )
    (comp (ref "R294")
      (value "4k7")
      (footprint "RESC1005X40N")
      (description "Resistor - 1%")
      (fields
        (field (name "MANUFACTURER PART NUMBER") "R0402_4K7_1%_0.0625W_100PPM")
        (field (name "MANUFACTURER") "GENERIC")
        (field (name "AUTHOR") "CERN DEM JLC")
      )
      (libsource (lib "Resistors") (part "Resistor - 1%"))
    )
    (comp (ref "R295")
      (value "22")
      (footprint "RESC1005X40N")
      (description "Resistor - 1%")
      (fields
        (field (name "MANUFACTURER PART NUMBER") "R0402_22R_1%_0.0625W_100PPM")
        (field (name "MANUFACTURER") "GENERIC")
        (field (name "AUTHOR") "CERN DEM JLC")
      )
      (libsource (lib "Resistors") (part "Resistor - 1%"))
    )
    (comp (ref "R1000")
      (value "4k7")
      (footprint "RESC1005X40N")
      (description "Resistor - 1%")
      (fields
        (field (name "MANUFACTURER PART NUMBER") "R0402_4K7_1%_0.0625W_100PPM")
        (field (name "MANUFACTURER") "GENERIC")
        (field (name "AUTHOR") "CERN DEM JLC")
      )
      (libsource (lib "Resistors") (part "Resistor - 1%"))
    )
    (comp (ref "R1001")
      (value "0")
      (footprint "RESC1005X40N")
      (description "Resistor")
      (fields
        (field (name "PART NUMBER") "R0402_0R_JUMPER")
        (field (name "MANUFACTURER") "GENERIC")
        (field (name "AUTHOR") "CERN DEM JLC")
      )
      (libsource (lib "Resistors") (part "Resistor"))
    )
    (comp (ref "W1")
      (value "Header 4")
      (footprint "SAMTEC_MTLW-104-07-L-S-250")
      (description "4 Mini Wire-Wrap Contact Strip Header")
      (fields
        (field (name "MANUFACTURER PART NUMBER") "MTLW-104-07-L-S-250")
        (field (name "MANUFACTURER") "SAMTEC")
        (field (name "AUTHOR") "CERN DEM JLC")
      )
      (libsource (lib "Connectors") (part "Wire-Wrap Contact x4"))
    )
  )
  (nets
    (net (code "5") (name "/AVDD15") (class "Default")
      (node (ref "C417") (pin "2") (pinfunction "2_2") (pintype "passive"))
      (node (ref "C418") (pin "2") (pinfunction "2_2") (pintype "passive"))
      (node (ref "C419") (pin "2") (pinfunction "2_2") (pintype "passive"))
      (node (ref "C420") (pin "2") (pinfunction "2_2") (pintype "passive"))
      (node (ref "C421") (pin "2") (pinfunction "2_2") (pintype "passive"))
      (node (ref "C422") (pin "2") (pinfunction "2_2") (pintype "passive"))
      (node (ref "C423") (pin "2") (pinfunction "2_2") (pintype "passive"))
      (node (ref "C424") (pin "2") (pinfunction "2_2") (pintype "passive"))
      (node (ref "IC26") (pin "106") (pinfunction "P0_AVDD15_106") (pintype "power_in"))
      (node (ref "IC26") (pin "19") (pinfunction "P4_AVDD15_19") (pintype "power_in"))
      (node (ref "IC26") (pin "27") (pinfunction "AVDD15_27") (pintype "power_in"))
      (node (ref "IC26") (pin "3") (pinfunction "P1_AVDD15_3") (pintype "power_in"))
      (node (ref "IC26") (pin "33") (pinfunction "AVDD15_33") (pintype "power_in"))
      (node (ref "IC26") (pin "60") (pinfunction "VOUT15_60") (pintype "power_in"))
      (node (ref "IC26") (pin "61") (pinfunction "VOUT15_SEN_61") (pintype "power_in"))
      (node (ref "IC26") (pin "9") (pinfunction "P3_AVDD15_9") (pintype "power_in"))
    )
    (net (code "6") (name "/MII1_COL") (class "Default")
      (node (ref "R242") (pin "2") (pinfunction "2_2") (pintype "passive"))
    )
    (net (code "7") (name "/MII1_CRS") (class "Default")
      (node (ref "R241") (pin "2") (pinfunction "2_2") (pintype "passive"))
    )
    (net (code "8") (name "/MII1_INT") (class "Default")
      (node (ref "IC26") (pin "56") (pinfunction "INTn_56") (pintype "output"))
      (node (ref "R288") (pin "2") (pinfunction "2_2") (pintype "passive"))
    )
    (net (code "9") (name "/MII1_MDC") (class "Default")
      (node (ref "IC26") (pin "55") (pinfunction "MDC_CPU_55") (pintype "input"))
      (node (ref "IC47") (pin "8") (pinfunction "B1_8") (pintype "bidirectional"))
      (node (ref "R281") (pin "2") (pinfunction "2_2") (pintype "passive"))
    )
    (net (code "10") (name "/MII1_MDIO") (class "Default")
      (node (ref "IC26") (pin "54") (pinfunction "MDIO_CPU_54") (pintype "bidirectional"))
      (node (ref "IC47") (pin "1") (pinfunction "B2_1") (pintype "bidirectional"))
      (node (ref "R285") (pin "2") (pinfunction "2_2") (pintype "passive"))
    )
    (net (code "11") (name "/MII1_MODE") (class "Default")
      (node (ref "R254") (pin "2") (pinfunction "2_2") (pintype "passive"))
    )
    (net (code "12") (name "/MII1_RXD0") (class "Default")
      (node (ref "R253") (pin "2") (pinfunction "2_2") (pintype "passive"))
    )
    (net (code "13") (name "/MII1_RXD1") (class "Default")
      (node (ref "R251") (pin "2") (pinfunction "2_2") (pintype "passive"))
    )
    (net (code "14") (name "/MII1_RXD2") (class "Default")
      (node (ref "R249") (pin "2") (pinfunction "2_2") (pintype "passive"))
    )
    (net (code "15") (name "/MII1_RXD3") (class "Default")
      (node (ref "R247") (pin "2") (pinfunction "2_2") (pintype "passive"))
    )
    (net (code "16") (name "/MII1_RX_CLK") (class "Default")
      (node (ref "R245") (pin "2") (pinfunction "2_2") (pintype "passive"))
    )
    (net (code "17") (name "/MII1_RX_DV") (class "Default")
      (node (ref "R244") (pin "2") (pinfunction "2_2") (pintype "passive"))
    )
    (net (code "18") (name "/MII1_RX_ER") (class "Default")
      (node (ref "R234") (pin "2") (pinfunction "2_2") (pintype "passive"))
    )
    (net (code "19") (name "/MII1_TXD0") (class "Default")
      (node (ref "R239") (pin "2") (pinfunction "2_2") (pintype "passive"))
    )
    (net (code "20") (name "/MII1_TXD1") (class "Default")
      (node (ref "R238") (pin "2") (pinfunction "2_2") (pintype "passive"))
    )
    (net (code "21") (name "/MII1_TXD2") (class "Default")
      (node (ref "R237") (pin "2") (pinfunction "2_2") (pintype "passive"))
    )
    (net (code "22") (name "/MII1_TXD3") (class "Default")
      (node (ref "R236") (pin "2") (pinfunction "2_2") (pintype "passive"))
    )
    (net (code "23") (name "/MII1_TX_CLK") (class "Default")
      (node (ref "R235") (pin "2") (pinfunction "2_2") (pintype "passive"))
    )
    (net (code "24") (name "/MII1_TX_EN") (class "Default")
      (node (ref "R240") (pin "2") (pinfunction "2_2") (pintype "passive"))
    )
    (net (code "25") (name "/P0_RX_N") (class "Default")
      (node (ref "C405") (pin "2") (pinfunction "2_2") (pintype "passive"))
      (node (ref "IC26") (pin "108") (pinfunction "P0_S_RXN_108") (pintype "input"))
    )
    (net (code "26") (name "/P0_RX_P") (class "Default")
      (node (ref "C404") (pin "2") (pinfunction "2_2") (pintype "passive"))
      (node (ref "IC26") (pin "107") (pinfunction "P0_S_RXP_107") (pintype "input"))
    )
    (net (code "27") (name "/P0_TX_N") (class "Default")
      (node (ref "C407") (pin "2") (pinfunction "2_2") (pintype "passive"))
      (node (ref "IC26") (pin "105") (pinfunction "P0_S_TXN_105") (pintype "input"))
    )
    (net (code "28") (name "/P0_TX_P") (class "Default")
      (node (ref "C406") (pin "2") (pinfunction "2_2") (pintype "passive"))
      (node (ref "IC26") (pin "104") (pinfunction "P0_S_TXP_104") (pintype "input"))
    )
    (net (code "29") (name "/P1_RX_N") (class "Default")
      (node (ref "C409") (pin "2") (pinfunction "2_2") (pintype "passive"))
      (node (ref "IC26") (pin "5") (pinfunction "P1_S_RXN_5") (pintype "input"))
    )
    (net (code "30") (name "/P1_RX_P") (class "Default")
      (node (ref "C408") (pin "2") (pinfunction "2_2") (pintype "passive"))
      (node (ref "IC26") (pin "4") (pinfunction "P1_S_RXP_4") (pintype "input"))
    )
    (net (code "31") (name "/P1_TX_N") (class "Default")
      (node (ref "C411") (pin "2") (pinfunction "2_2") (pintype "passive"))
      (node (ref "IC26") (pin "2") (pinfunction "P1_S_TXN_2") (pintype "output"))
    )
    (net (code "32") (name "/P1_TX_P") (class "Default")
      (node (ref "C410") (pin "2") (pinfunction "2_2") (pintype "passive"))
      (node (ref "IC26") (pin "1") (pinfunction "P1_S_TXP_1") (pintype "output"))
    )
    (net (code "33") (name "/P3_MDI0_N") (class "Default")
      (node (ref "IC26") (pin "8") (pinfunction "P3_MDIN0_8") (pintype "input"))
      (node (ref "J7") (pin "3") (pinfunction "3_3") (pintype "bidirectional"))
    )
    (net (code "34") (name "/P3_MDI0_P") (class "Default")
      (node (ref "IC26") (pin "7") (pinfunction "P3_MDIP0_7") (pintype "input"))
      (node (ref "J7") (pin "2") (pinfunction "2_2") (pintype "bidirectional"))
    )
    (net (code "35") (name "/P3_MDI1_N") (class "Default")
      (node (ref "IC26") (pin "11") (pinfunction "P3_MDIN1_11") (pintype "input"))
      (node (ref "J7") (pin "6") (pinfunction "6_6") (pintype "bidirectional"))
    )
    (net (code "36") (name "/P3_MDI1_P") (class "Default")
      (node (ref "IC26") (pin "10") (pinfunction "P3_MDIP1_10") (pintype "input"))
      (node (ref "J7") (pin "5") (pinfunction "5_5") (pintype "bidirectional"))
    )
    (net (code "37") (name "/P3_MDI2_N") (class "Default")
      (node (ref "IC26") (pin "14") (pinfunction "P3_MDIN2_14") (pintype "input"))
      (node (ref "J7") (pin "9") (pinfunction "9_9") (pintype "bidirectional"))
    )
    (net (code "38") (name "/P3_MDI2_P") (class "Default")
      (node (ref "IC26") (pin "13") (pinfunction "P3_MDIP2_13") (pintype "input"))
      (node (ref "J7") (pin "8") (pinfunction "8_8") (pintype "bidirectional"))
    )
    (net (code "39") (name "/P3_MDI3_N") (class "Default")
      (node (ref "IC26") (pin "16") (pinfunction "P3_MDIN3_16") (pintype "input"))
      (node (ref "J7") (pin "12") (pinfunction "12_12") (pintype "bidirectional"))
    )
    (net (code "40") (name "/P3_MDI3_P") (class "Default")
      (node (ref "IC26") (pin "15") (pinfunction "P3_MDIP3_15") (pintype "input"))
      (node (ref "J7") (pin "11") (pinfunction "11_11") (pintype "bidirectional"))
    )
    (net (code "41") (name "/PHY_RESETn") (class "Default")
      (node (ref "IC26") (pin "103") (pinfunction "RESETn_103") (pintype "input"))
    )
    (net (code "43") (name "/RGMII1_RXD0") (class "Default")
      (node (ref "R280") (pin "2") (pinfunction "2_2") (pintype "passive"))
    )
    (net (code "44") (name "/RGMII1_RXD1") (class "Default")
      (node (ref "R276") (pin "2") (pinfunction "2_2") (pintype "passive"))
    )
    (net (code "45") (name "/RGMII1_RXD2") (class "Default")
      (node (ref "R274") (pin "2") (pinfunction "2_2") (pintype "passive"))
    )
    (net (code "46") (name "/RGMII1_RXD3") (class "Default")
      (node (ref "R272") (pin "2") (pinfunction "2_2") (pintype "passive"))
    )
    (net (code "47") (name "/RGMII1_RX_CLK") (class "Default")
      (node (ref "R259") (pin "2") (pinfunction "2_2") (pintype "passive"))
    )
    (net (code "48") (name "/RGMII1_RX_CTL") (class "Default")
      (node (ref "R264") (pin "2") (pinfunction "2_2") (pintype "passive"))
    )
    (net (code "49") (name "/RGMII1_TXD0") (class "Default")
      (node (ref "IC26") (pin "92") (pinfunction "P6_IND4/P2_IND0/GPIO11_92") (pintype "input"))
    )
    (net (code "50") (name "/RGMII1_TXD1") (class "Default")
      (node (ref "IC26") (pin "93") (pinfunction "P6_IND5/P2_IND1/GPIO12_93") (pintype "input"))
    )
    (net (code "51") (name "/RGMII1_TXD2") (class "Default")
      (node (ref "IC26") (pin "94") (pinfunction "P6_IND6/P2_IND2/GPIO13_94") (pintype "input"))
    )
    (net (code "52") (name "/RGMII1_TXD3") (class "Default")
      (node (ref "IC26") (pin "95") (pinfunction "P6_IND7/P2_IND3/GPIO14_95") (pintype "input"))
    )
    (net (code "53") (name "/RGMII1_TX_CLK") (class "Default")
      (node (ref "IC26") (pin "90") (pinfunction "P6_COL/P2_INCLK/GPIO9_90") (pintype "input"))
    )
    (net (code "54") (name "/RGMII1_TX_CTL") (class "Default")
      (node (ref "IC26") (pin "91") (pinfunction "P6_CRS/P2_INDV/GPIO10_91") (pintype "input"))
    )
    (net (code "55") (name "/RGMII2_MDC") (class "Default")
      (node (ref "IC47") (pin "5") (pinfunction "A1_5") (pintype "bidirectional"))
      (node (ref "R256") (pin "1") (pinfunction "1_1") (pintype "passive"))
    )
    (net (code "56") (name "/RGMII2_MDIO") (class "Default")
      (node (ref "IC47") (pin "4") (pinfunction "A2_4") (pintype "bidirectional"))
      (node (ref "R255") (pin "1") (pinfunction "1_1") (pintype "passive"))
    )
    (net (code "57") (name "/RGMII2_RXD0") (class "Default")
      (node (ref "R295") (pin "2") (pinfunction "2_2") (pintype "passive"))
    )
    (net (code "58") (name "/RGMII2_RXD1") (class "Default")
      (node (ref "R290") (pin "2") (pinfunction "2_2") (pintype "passive"))
    )
    (net (code "59") (name "/RGMII2_RXD2") (class "Default")
      (node (ref "R287") (pin "2") (pinfunction "2_2") (pintype "passive"))
    )
    (net (code "60") (name "/RGMII2_RXD3") (class "Default")
      (node (ref "R283") (pin "2") (pinfunction "2_2") (pintype "passive"))
    )
    (net (code "61") (name "/RGMII2_RX_CLK") (class "Default")
      (node (ref "R262") (pin "2") (pinfunction "2_2") (pintype "passive"))
    )
    (net (code "62") (name "/RGMII2_RX_CTL") (class "Default")
      (node (ref "R261") (pin "2") (pinfunction "2_2") (pintype "passive"))
    )
    (net (code "63") (name "/RGMII2_TXD0") (class "Default")
      (node (ref "IC26") (pin "78") (pinfunction "P6_IND0_78") (pintype "input"))
    )
    (net (code "64") (name "/RGMII2_TXD1") (class "Default")
      (node (ref "IC26") (pin "79") (pinfunction "P6_IND1_79") (pintype "input"))
    )
    (net (code "65") (name "/RGMII2_TXD2") (class "Default")
      (node (ref "IC26") (pin "80") (pinfunction "P6_IND2_80") (pintype "input"))
    )
    (net (code "66") (name "/RGMII2_TXD3") (class "Default")
      (node (ref "IC26") (pin "81") (pinfunction "P6_IND3_81") (pintype "input"))
    )
    (net (code "67") (name "/RGMII2_TX_CLK") (class "Default")
      (node (ref "IC26") (pin "76") (pinfunction "P6_INCLK_76") (pintype "input"))
    )
    (net (code "68") (name "/RGMII2_TX_CTL") (class "Default")
      (node (ref "IC26") (pin "77") (pinfunction "P6_INDV_77") (pintype "input"))
    )
    (net (code "69") (name "/RX0_N") (class "Default")
      (node (ref "C1007") (pin "1") (pinfunction "1_1") (pintype "passive"))
      (node (ref "C405") (pin "1") (pinfunction "1_1") (pintype "passive"))
    )
    (net (code "70") (name "/RX0_P") (class "Default")
      (node (ref "C1005") (pin "1") (pinfunction "1_1") (pintype "passive"))
      (node (ref "C404") (pin "1") (pinfunction "1_1") (pintype "passive"))
    )
    (net (code "71") (name "/RX0_SoC_N") (class "Default")
      (node (ref "C1007") (pin "2") (pinfunction "2_2") (pintype "passive"))
    )
    (net (code "72") (name "/RX0_SoC_P") (class "Default")
      (node (ref "C1005") (pin "2") (pinfunction "2_2") (pintype "passive"))
    )
    (net (code "73") (name "/RX1_N") (class "Default")
      (node (ref "C409") (pin "1") (pinfunction "1_1") (pintype "passive"))
    )
    (net (code "74") (name "/RX1_P") (class "Default")
      (node (ref "C408") (pin "1") (pinfunction "1_1") (pintype "passive"))
    )
    (net (code "75") (name "/SCL_ETH_SWITCH") (class "Default")
      (node (ref "IC26") (pin "98") (pinfunction "EE_CLK/C0_LED/FLOW_98") (pintype "output"))
      (node (ref "IC28") (pin "6") (pinfunction "SCL_6") (pintype "input"))
      (node (ref "LD3") (pin "2") (pinfunction "A_2") (pintype "passive"))
      (node (ref "R277") (pin "2") (pinfunction "2_2") (pintype "passive"))
      (node (ref "R278") (pin "1") (pinfunction "1_1") (pintype "passive"))
      (node (ref "W1") (pin "2") (pinfunction "2_2") (pintype "bidirectional"))
    )
    (net (code "76") (name "/SDA_ETH_SWITCH") (class "Default")
      (node (ref "IC26") (pin "97") (pinfunction "EE_DOUT/C1_LED/P4_LED0_97") (pintype "bidirectional"))
      (node (ref "IC28") (pin "5") (pinfunction "SDA_5") (pintype "bidirectional"))
      (node (ref "LD4") (pin "2") (pinfunction "A_2") (pintype "passive"))
      (node (ref "R291") (pin "2") (pinfunction "2_2") (pintype "passive"))
      (node (ref "W1") (pin "3") (pinfunction "3_3") (pintype "bidirectional"))
    )
    (net (code "77") (name "/TX0_N") (class "Default")
      (node (ref "C1029") (pin "1") (pinfunction "1_1") (pintype "passive"))
      (node (ref "C407") (pin "1") (pinfunction "1_1") (pintype "passive"))
    )
    (net (code "78") (name "/TX0_P") (class "Default")
      (node (ref "C1028") (pin "1") (pinfunction "1_1") (pintype "passive"))
      (node (ref "C406") (pin "1") (pinfunction "1_1") (pintype "passive"))
    )
    (net (code "79") (name "/TX0_SoC_N") (class "Default")
      (node (ref "C1029") (pin "2") (pinfunction "2_2") (pintype "passive"))
    )
    (net (code "80") (name "/TX0_SoC_P") (class "Default")
      (node (ref "C1028") (pin "2") (pinfunction "2_2") (pintype "passive"))
    )
    (net (code "81") (name "/TX1_N") (class "Default")
      (node (ref "C411") (pin "1") (pinfunction "1_1") (pintype "passive"))
    )
    (net (code "82") (name "/TX1_P") (class "Default")
      (node (ref "C410") (pin "1") (pinfunction "1_1") (pintype "passive"))
    )
    (net (code "83") (name "/VDD_CORE") (class "Default")
      (node (ref "C426") (pin "2") (pinfunction "2_2") (pintype "passive"))
      (node (ref "C427") (pin "2") (pinfunction "2_2") (pintype "passive"))
      (node (ref "C428") (pin "2") (pinfunction "2_2") (pintype "passive"))
      (node (ref "C429") (pin "2") (pinfunction "2_2") (pintype "passive"))
      (node (ref "IC26") (pin "38") (pinfunction "VDD_CORE_38") (pintype "power_in"))
      (node (ref "IC26") (pin "62") (pinfunction "VOUT11_SEN_62") (pintype "power_in"))
      (node (ref "IC26") (pin "63") (pinfunction "VOUT11_63") (pintype "power_in"))
      (node (ref "IC26") (pin "65") (pinfunction "VDD_CORE_65") (pintype "power_in"))
      (node (ref "IC26") (pin "96") (pinfunction "VDD_CORE_96") (pintype "power_in"))
    )
    (net (code "87") (name "GND") (class "Default")
      (node (ref "C412") (pin "1") (pinfunction "1_1") (pintype "passive"))
      (node (ref "C413") (pin "1") (pinfunction "1_1") (pintype "passive"))
      (node (ref "C414") (pin "1") (pinfunction "1_1") (pintype "passive"))
      (node (ref "C415") (pin "1") (pinfunction "1_1") (pintype "passive"))
      (node (ref "C416") (pin "1") (pinfunction "1_1") (pintype "passive"))
      (node (ref "C417") (pin "1") (pinfunction "1_1") (pintype "passive"))
      (node (ref "C418") (pin "1") (pinfunction "1_1") (pintype "passive"))
      (node (ref "C419") (pin "1") (pinfunction "1_1") (pintype "passive"))
      (node (ref "C420") (pin "1") (pinfunction "1_1") (pintype "passive"))
      (node (ref "C421") (pin "1") (pinfunction "1_1") (pintype "passive"))
      (node (ref "C422") (pin "1") (pinfunction "1_1") (pintype "passive"))
      (node (ref "C423") (pin "1") (pinfunction "1_1") (pintype "passive"))
      (node (ref "C424") (pin "1") (pinfunction "1_1") (pintype "passive"))
      (node (ref "C426") (pin "1") (pinfunction "1_1") (pintype "passive"))
      (node (ref "C427") (pin "1") (pinfunction "1_1") (pintype "passive"))
      (node (ref "C428") (pin "1") (pinfunction "1_1") (pintype "passive"))
      (node (ref "C429") (pin "1") (pinfunction "1_1") (pintype "passive"))
      (node (ref "C430") (pin "1") (pinfunction "1_1") (pintype "passive"))
      (node (ref "C431") (pin "1") (pinfunction "1_1") (pintype "passive"))
      (node (ref "C432") (pin "1") (pinfunction "1_1") (pintype "passive"))
      (node (ref "C433") (pin "1") (pinfunction "1_1") (pintype "passive"))
      (node (ref "C434") (pin "1") (pinfunction "1_1") (pintype "passive"))
      (node (ref "C435") (pin "1") (pinfunction "1_1") (pintype "passive"))
      (node (ref "C436") (pin "1") (pinfunction "1_1") (pintype "passive"))
      (node (ref "C437") (pin "1") (pinfunction "1_1") (pintype "passive"))
      (node (ref "C438") (pin "1") (pinfunction "1_1") (pintype "passive"))
      (node (ref "C439") (pin "1") (pinfunction "1_1") (pintype "passive"))
      (node (ref "C440") (pin "1") (pinfunction "1_1") (pintype "passive"))
      (node (ref "C441") (pin "1") (pinfunction "1_1") (pintype "passive"))
      (node (ref "C442") (pin "1") (pinfunction "1_1") (pintype "passive"))
      (node (ref "C443") (pin "1") (pinfunction "1_1") (pintype "passive"))
      (node (ref "C444") (pin "1") (pinfunction "1_1") (pintype "passive"))
      (node (ref "IC26") (pin "109") (pinfunction "EP_109") (pintype "power_in"))
      (node (ref "IC26") (pin "36") (pinfunction "XTAL_GND_36") (pintype "input"))
      (node (ref "IC26") (pin "6") (pinfunction "VSS_6") (pintype "power_in"))
      (node (ref "IC28") (pin "1") (pinfunction "A0_1") (pintype "input"))
      (node (ref "IC28") (pin "2") (pinfunction "A1_2") (pintype "input"))
      (node (ref "IC28") (pin "3") (pinfunction "A2_3") (pintype "input"))
      (node (ref "IC28") (pin "4") (pinfunction "VSS_4") (pintype "power_in"))
      (node (ref "IC28") (pin "7") (pinfunction "WP_7") (pintype "input"))
      (node (ref "IC47") (pin "2") (pinfunction "GND_2") (pintype "power_in"))
      (node (ref "J7") (pin "1") (pinfunction "1_1") (pintype "bidirectional"))
      (node (ref "J7") (pin "10") (pinfunction "10_10") (pintype "bidirectional"))
      (node (ref "J7") (pin "13") (pinfunction "13_13") (pintype "bidirectional"))
      (node (ref "J7") (pin "4") (pinfunction "4_4") (pintype "bidirectional"))
      (node (ref "Q2") (pin "2") (pinfunction "GND_2") (pintype "power_in"))
      (node (ref "Q2") (pin "4") (pinfunction "GND_4") (pintype "power_in"))
      (node (ref "R234") (pin "1") (pinfunction "1_1") (pintype "passive"))
      (node (ref "R243") (pin "2") (pinfunction "2_2") (pintype "passive"))
      (node (ref "R248") (pin "2") (pinfunction "2_2") (pintype "passive"))
      (node (ref "R250") (pin "2") (pinfunction "2_2") (pintype "passive"))
      (node (ref "R258") (pin "1") (pinfunction "1_1") (pintype "passive"))
      (node (ref "R260") (pin "2") (pinfunction "2_2") (pintype "passive"))
      (node (ref "R263") (pin "2") (pinfunction "2_2") (pintype "passive"))
      (node (ref "R267") (pin "2") (pinfunction "2_2") (pintype "passive"))
      (node (ref "R268") (pin "1") (pinfunction "1_1") (pintype "passive"))
      (node (ref "R270") (pin "1") (pinfunction "1_1") (pintype "passive"))
      (node (ref "R278") (pin "2") (pinfunction "2_2") (pintype "passive"))
      (node (ref "R282") (pin "2") (pinfunction "2_2") (pintype "passive"))
      (node (ref "R293") (pin "1") (pinfunction "1_1") (pintype "passive"))
      (node (ref "W1") (pin "4") (pinfunction "4_4") (pintype "bidirectional"))
    )
    (net (code "88") (name "Net-(IC26-CBOT)") (class "Default")
      (node (ref "C425") (pin "1") (pinfunction "1_1") (pintype "passive"))
      (node (ref "IC26") (pin "64") (pinfunction "CBOT_64") (pintype "power_in"))
    )
    (net (code "89") (name "Net-(IC26-CTOP)") (class "Default")
      (node (ref "C425") (pin "2") (pinfunction "2_2") (pintype "passive"))
      (node (ref "IC26") (pin "59") (pinfunction "CTOP_59") (pintype "power_in"))
    )
    (net (code "90") (name "Net-(IC26-GPIO3{slash}P0_SMODE)") (class "Default")
      (node (ref "IC26") (pin "68") (pinfunction "GPIO3/P0_SMODE_68") (pintype "input"))
      (node (ref "R269") (pin "1") (pinfunction "1_1") (pintype "passive"))
    )
    (net (code "91") (name "Net-(IC26-GPIO4{slash}P1_SMODE)") (class "Default")
      (node (ref "IC26") (pin "67") (pinfunction "GPIO4/P1_SMODE_67") (pintype "input"))
      (node (ref "R265") (pin "1") (pinfunction "1_1") (pintype "passive"))
    )
    (net (code "92") (name "Net-(IC26-P2_OUTEN{slash}EEE_WP)") (class "Default")
      (node (ref "IC26") (pin "87") (pinfunction "P2_OUTEN/EEE_WP_87") (pintype "output"))
      (node (ref "R263") (pin "1") (pinfunction "1_1") (pintype "passive"))
      (node (ref "R264") (pin "1") (pinfunction "1_1") (pintype "passive"))
    )
    (net (code "93") (name "Net-(IC26-P5_COL{slash}MDIO_PHY{slash}GPIO7)") (class "Default")
      (node (ref "IC26") (pin "52") (pinfunction "P5_COL/MDIO_PHY/GPIO7_52") (pintype "input"))
      (node (ref "R242") (pin "1") (pinfunction "1_1") (pintype "passive"))
    )
    (net (code "94") (name "Net-(IC26-P5_CRS{slash}MDC_PHY{slash}GPIO8)") (class "Default")
      (node (ref "IC26") (pin "53") (pinfunction "P5_CRS/MDC_PHY/GPIO8_53") (pintype "input"))
      (node (ref "R1001") (pin "2") (pinfunction "2_2") (pintype "passive"))
      (node (ref "R241") (pin "1") (pinfunction "1_1") (pintype "passive"))
    )
    (net (code "95") (name "Net-(IC26-P5_INCLK{slash}GPIO1)") (class "Default")
      (node (ref "IC26") (pin "45") (pinfunction "P5_INCLK/GPIO1_45") (pintype "input"))
      (node (ref "R235") (pin "1") (pinfunction "1_1") (pintype "passive"))
    )
    (net (code "96") (name "Net-(IC26-P5_IND0)") (class "Default")
      (node (ref "IC26") (pin "48") (pinfunction "P5_IND0_48") (pintype "input"))
      (node (ref "R239") (pin "1") (pinfunction "1_1") (pintype "passive"))
    )
    (net (code "97") (name "Net-(IC26-P5_IND1)") (class "Default")
      (node (ref "IC26") (pin "49") (pinfunction "P5_IND1_49") (pintype "input"))
      (node (ref "R238") (pin "1") (pinfunction "1_1") (pintype "passive"))
    )
    (net (code "98") (name "Net-(IC26-P5_IND2{slash}GPIO5)") (class "Default")
      (node (ref "IC26") (pin "50") (pinfunction "P5_IND2/GPIO5_50") (pintype "input"))
      (node (ref "R237") (pin "1") (pinfunction "1_1") (pintype "passive"))
    )
    (net (code "99") (name "Net-(IC26-P5_IND3{slash}GPIO6)") (class "Default")
      (node (ref "IC26") (pin "51") (pinfunction "P5_IND3/GPIO6_51") (pintype "input"))
      (node (ref "R236") (pin "1") (pinfunction "1_1") (pintype "passive"))
    )
    (net (code "100") (name "Net-(IC26-P5_INDV{slash}GPIO2)") (class "Default")
      (node (ref "IC26") (pin "46") (pinfunction "P5_INDV/GPIO2_46") (pintype "input"))
      (node (ref "R240") (pin "1") (pinfunction "1_1") (pintype "passive"))
    )
    (net (code "101") (name "Net-(IC26-P5_OUTCLK{slash}GPIO0)") (class "Default")
      (node (ref "IC26") (pin "44") (pinfunction "P5_OUTCLK/GPIO0_44") (pintype "input"))
      (node (ref "R245") (pin "1") (pinfunction "1_1") (pintype "passive"))
    )
    (net (code "102") (name "Net-(IC26-P5_OUTD0{slash}P5_MODE0)") (class "Default")
      (node (ref "IC26") (pin "42") (pinfunction "P5_OUTD0/P5_MODE0_42") (pintype "output"))
      (node (ref "R252") (pin "1") (pinfunction "1_1") (pintype "passive"))
      (node (ref "R253") (pin "1") (pinfunction "1_1") (pintype "passive"))
    )
    (net (code "103") (name "Net-(IC26-P5_OUTD1{slash}P5_MODE1)") (class "Default")
      (node (ref "IC26") (pin "41") (pinfunction "P5_OUTD1/P5_MODE1_41") (pintype "output"))
      (node (ref "R250") (pin "1") (pinfunction "1_1") (pintype "passive"))
      (node (ref "R251") (pin "1") (pinfunction "1_1") (pintype "passive"))
    )
    (net (code "104") (name "Net-(IC26-P5_OUTD2{slash}P5_MODE2)") (class "Default")
      (node (ref "IC26") (pin "39") (pinfunction "P5_OUTD2/P5_MODE2_39") (pintype "output"))
      (node (ref "R248") (pin "1") (pinfunction "1_1") (pintype "passive"))
      (node (ref "R249") (pin "1") (pinfunction "1_1") (pintype "passive"))
    )
    (net (code "105") (name "Net-(IC26-P5_OUTD3{slash}P5_VDDOS1)") (class "Default")
      (node (ref "IC26") (pin "37") (pinfunction "P5_OUTD3/P5_VDDOS1_37") (pintype "output"))
      (node (ref "R246") (pin "1") (pinfunction "1_1") (pintype "passive"))
      (node (ref "R247") (pin "1") (pinfunction "1_1") (pintype "passive"))
    )
    (net (code "106") (name "Net-(IC26-P5_OUTEN{slash}P5_VDDOS0)") (class "Default")
      (node (ref "IC26") (pin "43") (pinfunction "P5_OUTEN/P5_VDDOS0_43") (pintype "output"))
      (node (ref "R1001") (pin "1") (pinfunction "1_1") (pintype "passive"))
      (node (ref "R243") (pin "1") (pinfunction "1_1") (pintype "passive"))
      (node (ref "R244") (pin "1") (pinfunction "1_1") (pintype "passive"))
    )
    (net (code "107") (name "Net-(IC26-P6_GTXCLK{slash}P2_OUTCLK{slash}ADDR0n)") (class "Default")
      (node (ref "IC26") (pin "88") (pinfunction "P6_GTXCLK/P2_OUTCLK/ADDR0n_88") (pintype "output"))
      (node (ref "R1000") (pin "1") (pinfunction "1_1") (pintype "passive"))
      (node (ref "R259") (pin "1") (pinfunction "1_1") (pintype "passive"))
    )
    (net (code "108") (name "Net-(IC26-P6_OUTCLK)") (class "Default")
      (node (ref "IC26") (pin "75") (pinfunction "P6_OUTCLK_75") (pintype "input"))
      (node (ref "R262") (pin "1") (pinfunction "1_1") (pintype "passive"))
    )
    (net (code "109") (name "Net-(IC26-P6_OUTD0{slash}P6_MODE0)") (class "Default")
      (node (ref "IC26") (pin "72") (pinfunction "P6_OUTD0/P6_MODE0_72") (pintype "output"))
      (node (ref "R294") (pin "1") (pinfunction "1_1") (pintype "passive"))
      (node (ref "R295") (pin "1") (pinfunction "1_1") (pintype "passive"))
    )
    (net (code "110") (name "Net-(IC26-P6_OUTD1{slash}P6_MODE1)") (class "Default")
      (node (ref "IC26") (pin "71") (pinfunction "P6_OUTD1/P6_MODE1_71") (pintype "output"))
      (node (ref "R289") (pin "1") (pinfunction "1_1") (pintype "passive"))
      (node (ref "R290") (pin "1") (pinfunction "1_1") (pintype "passive"))
    )
    (net (code "111") (name "Net-(IC26-P6_OUTD2{slash}P6_MODE2)") (class "Default")
      (node (ref "IC26") (pin "70") (pinfunction "P6_OUTD2/P6_MODE2_70") (pintype "output"))
      (node (ref "R286") (pin "1") (pinfunction "1_1") (pintype "passive"))
      (node (ref "R287") (pin "1") (pinfunction "1_1") (pintype "passive"))
    )
    (net (code "112") (name "Net-(IC26-P6_OUTD3{slash}P6_VDDOS1)") (class "Default")
      (node (ref "IC26") (pin "69") (pinfunction "P6_OUTD3/P6_VDDOS1_69") (pintype "output"))
      (node (ref "R282") (pin "1") (pinfunction "1_1") (pintype "passive"))
      (node (ref "R283") (pin "1") (pinfunction "1_1") (pintype "passive"))
    )
    (net (code "113") (name "Net-(IC26-P6_OUTD4{slash}P2_OUTD0{slash}ADDR1n)") (class "Default")
      (node (ref "IC26") (pin "86") (pinfunction "P6_OUTD4/P2_OUTD0/ADDR1n_86") (pintype "output"))
      (node (ref "R279") (pin "1") (pinfunction "1_1") (pintype "passive"))
      (node (ref "R280") (pin "1") (pinfunction "1_1") (pintype "passive"))
    )
    (net (code "114") (name "Net-(IC26-P6_OUTD5{slash}P2_OUTD1{slash}ADDR2n)") (class "Default")
      (node (ref "IC26") (pin "85") (pinfunction "P6_OUTD5/P2_OUTD1/ADDR2n_85") (pintype "output"))
      (node (ref "R275") (pin "1") (pinfunction "1_1") (pintype "passive"))
      (node (ref "R276") (pin "1") (pinfunction "1_1") (pintype "passive"))
    )
    (net (code "115") (name "Net-(IC26-P6_OUTD6{slash}P2_OUTD2{slash}ADDR3n)") (class "Default")
      (node (ref "IC26") (pin "84") (pinfunction "P6_OUTD6/P2_OUTD2/ADDR3n_84") (pintype "output"))
      (node (ref "R273") (pin "1") (pinfunction "1_1") (pintype "passive"))
      (node (ref "R274") (pin "1") (pinfunction "1_1") (pintype "passive"))
    )
    (net (code "116") (name "Net-(IC26-P6_OUTD7{slash}P2_OUTD3{slash}ADDR4n)") (class "Default")
      (node (ref "IC26") (pin "83") (pinfunction "P6_OUTD7/P2_OUTD3/ADDR4n_83") (pintype "output"))
      (node (ref "R271") (pin "1") (pinfunction "1_1") (pintype "passive"))
      (node (ref "R272") (pin "1") (pinfunction "1_1") (pintype "passive"))
    )
    (net (code "117") (name "Net-(IC26-P6_OUTEN{slash}P6_VDDOS0)") (class "Default")
      (node (ref "IC26") (pin "73") (pinfunction "P6_OUTEN/P6_VDDOS0_73") (pintype "output"))
      (node (ref "R260") (pin "1") (pinfunction "1_1") (pintype "passive"))
      (node (ref "R261") (pin "1") (pinfunction "1_1") (pintype "passive"))
    )
    (net (code "118") (name "Net-(IC26-R0_LED{slash}P0_LED0{slash}LED_SEL0)") (class "Default")
      (node (ref "IC26") (pin "102") (pinfunction "R0_LED/P0_LED0/LED_SEL0_102") (pintype "output"))
      (node (ref "R270") (pin "2") (pinfunction "2_2") (pintype "passive"))
    )
    (net (code "119") (name "Net-(IC26-R1_LED{slash}P1_LED0{slash}LED_SEL1)") (class "Default")
      (node (ref "IC26") (pin "101") (pinfunction "R1_LED/P1_LED0/LED_SEL1_101") (pintype "output"))
      (node (ref "R268") (pin "2") (pinfunction "2_2") (pintype "passive"))
    )
    (net (code "120") (name "Net-(IC26-R2_LED{slash}P3_LED0{slash}NO_CPU)") (class "Default")
      (node (ref "IC26") (pin "100") (pinfunction "R2_LED/P3_LED0/NO_CPU_100") (pintype "output"))
      (node (ref "R266") (pin "2") (pinfunction "2_2") (pintype "passive"))
      (node (ref "R267") (pin "1") (pinfunction "1_1") (pintype "passive"))
      (node (ref "R284") (pin "2") (pinfunction "2_2") (pintype "passive"))
      (node (ref "R292") (pin "2") (pinfunction "2_2") (pintype "passive"))
    )
    (net (code "121") (name "Net-(IC26-RSET)") (class "Default")
      (node (ref "IC26") (pin "28") (pinfunction "RSET_28") (pintype "input"))
      (node (ref "R258") (pin "2") (pinfunction "2_2") (pintype "passive"))
    )
    (net (code "122") (name "Net-(IC26-TEST)") (class "Default")
      (node (ref "IC26") (pin "66") (pinfunction "TEST_66") (pintype "input"))
      (node (ref "R293") (pin "2") (pinfunction "2_2") (pintype "passive"))
    )
    (net (code "123") (name "Net-(IC26-XTAL_IN)") (class "Default")
      (node (ref "C414") (pin "2") (pinfunction "2_2") (pintype "passive"))
      (node (ref "IC26") (pin "34") (pinfunction "XTAL_IN_34") (pintype "input"))
      (node (ref "Q2") (pin "3") (pinfunction "X_3") (pintype "passive"))
    )
    (net (code "124") (name "Net-(IC26-XTAL_OUT)") (class "Default")
      (node (ref "C415") (pin "2") (pinfunction "2_2") (pintype "passive"))
      (node (ref "IC26") (pin "35") (pinfunction "XTAL_OUT_35") (pintype "output"))
      (node (ref "Q2") (pin "1") (pinfunction "X_1") (pintype "passive"))
    )
    (net (code "125") (name "Net-(IC47-OE)") (class "Default")
      (node (ref "IC47") (pin "6") (pinfunction "OE_6") (pintype "input"))
      (node (ref "R254") (pin "1") (pinfunction "1_1") (pintype "passive"))
    )
    (net (code "126") (name "Net-(LD3-C)") (class "Default")
      (node (ref "LD3") (pin "1") (pinfunction "C_1") (pintype "passive"))
      (node (ref "R284") (pin "1") (pinfunction "1_1") (pintype "passive"))
    )
    (net (code "127") (name "Net-(LD4-C)") (class "Default")
      (node (ref "LD4") (pin "1") (pinfunction "C_1") (pintype "passive"))
      (node (ref "R292") (pin "1") (pinfunction "1_1") (pintype "passive"))
    )
    (net (code "128") (name "P1V8") (class "Default")
      (node (ref "C412") (pin "2") (pinfunction "2_2") (pintype "passive"))
      (node (ref "C441") (pin "2") (pinfunction "2_2") (pintype "passive"))
      (node (ref "C442") (pin "2") (pinfunction "2_2") (pintype "passive"))
      (node (ref "C443") (pin "2") (pinfunction "2_2") (pintype "passive"))
      (node (ref "C444") (pin "2") (pinfunction "2_2") (pintype "passive"))
      (node (ref "IC26") (pin "74") (pinfunction "P6_VDDO_74") (pintype "power_in"))
      (node (ref "IC26") (pin "82") (pinfunction "P6_VDDO_82") (pintype "power_in"))
      (node (ref "IC26") (pin "89") (pinfunction "P6_VDDO_89") (pintype "power_in"))
      (node (ref "IC47") (pin "3") (pinfunction "Vcca_3") (pintype "power_in"))
      (node (ref "R1000") (pin "2") (pinfunction "2_2") (pintype "passive"))
      (node (ref "R255") (pin "2") (pinfunction "2_2") (pintype "passive"))
      (node (ref "R256") (pin "2") (pinfunction "2_2") (pintype "passive"))
      (node (ref "R265") (pin "2") (pinfunction "2_2") (pintype "passive"))
      (node (ref "R269") (pin "2") (pinfunction "2_2") (pintype "passive"))
      (node (ref "R271") (pin "2") (pinfunction "2_2") (pintype "passive"))
      (node (ref "R273") (pin "2") (pinfunction "2_2") (pintype "passive"))
      (node (ref "R275") (pin "2") (pinfunction "2_2") (pintype "passive"))
      (node (ref "R279") (pin "2") (pinfunction "2_2") (pintype "passive"))
      (node (ref "R286") (pin "2") (pinfunction "2_2") (pintype "passive"))
      (node (ref "R289") (pin "2") (pinfunction "2_2") (pintype "passive"))
      (node (ref "R294") (pin "2") (pinfunction "2_2") (pintype "passive"))
    )
    (net (code "129") (name "P3V3") (class "Default")
      (node (ref "L34") (pin "1") (pinfunction "1_1") (pintype "passive"))
    )
    (net (code "130") (name "P3V3AVDD") (class "Default")
      (node (ref "C434") (pin "2") (pinfunction "2_2") (pintype "passive"))
      (node (ref "C435") (pin "2") (pinfunction "2_2") (pintype "passive"))
      (node (ref "C436") (pin "2") (pinfunction "2_2") (pintype "passive"))
      (node (ref "C437") (pin "2") (pinfunction "2_2") (pintype "passive"))
      (node (ref "C438") (pin "2") (pinfunction "2_2") (pintype "passive"))
      (node (ref "C439") (pin "2") (pinfunction "2_2") (pintype "passive"))
      (node (ref "C440") (pin "2") (pinfunction "2_2") (pintype "passive"))
      (node (ref "IC26") (pin "12") (pinfunction "P3_AVDD33_12") (pintype "power_in"))
      (node (ref "IC26") (pin "22") (pinfunction "P4_AVDD33_22") (pintype "power_in"))
      (node (ref "IC26") (pin "57") (pinfunction "VDD33_PLL_57") (pintype "power_in"))
      (node (ref "IC26") (pin "58") (pinfunction "VDD33_58") (pintype "power_in"))
      (node (ref "L35") (pin "2") (pinfunction "2_2") (pintype "passive"))
    )
    (net (code "131") (name "P3V3_SW") (class "Default")
      (node (ref "C413") (pin "2") (pinfunction "2_2") (pintype "passive"))
      (node (ref "C416") (pin "2") (pinfunction "2_2") (pintype "passive"))
      (node (ref "C430") (pin "2") (pinfunction "2_2") (pintype "passive"))
      (node (ref "C431") (pin "2") (pinfunction "2_2") (pintype "passive"))
      (node (ref "C432") (pin "2") (pinfunction "2_2") (pintype "passive"))
      (node (ref "C433") (pin "2") (pinfunction "2_2") (pintype "passive"))
      (node (ref "IC26") (pin "40") (pinfunction "P5_VDDO_40") (pintype "power_in"))
      (node (ref "IC26") (pin "47") (pinfunction "P5_VDDO_47") (pintype "power_in"))
      (node (ref "IC26") (pin "99") (pinfunction "EE_VDDO_99") (pintype "power_in"))
      (node (ref "IC28") (pin "8") (pinfunction "VCC_8") (pintype "power_in"))
      (node (ref "IC47") (pin "7") (pinfunction "Vccb_7") (pintype "power_in"))
      (node (ref "J7") (pin "7") (pinfunction "7_7") (pintype "bidirectional"))
      (node (ref "L34") (pin "2") (pinfunction "2_2") (pintype "passive"))
      (node (ref "L35") (pin "1") (pinfunction "1_1") (pintype "passive"))
      (node (ref "R246") (pin "2") (pinfunction "2_2") (pintype "passive"))
      (node (ref "R252") (pin "2") (pinfunction "2_2") (pintype "passive"))
      (node (ref "R266") (pin "1") (pinfunction "1_1") (pintype "passive"))
      (node (ref "R277") (pin "1") (pinfunction "1_1") (pintype "passive"))
      (node (ref "R281") (pin "1") (pinfunction "1_1") (pintype "passive"))
      (node (ref "R285") (pin "1") (pinfunction "1_1") (pintype "passive"))
      (node (ref "R288") (pin "1") (pinfunction "1_1") (pintype "passive"))
      (node (ref "R291") (pin "1") (pinfunction "1_1") (pintype "passive"))
      (node (ref "W1") (pin "1") (pinfunction "1_1") (pintype "bidirectional"))
    )
    (net (code "132") (name "unconnected-(IC26-NC-Pad29)") (class "Default")
      (node (ref "IC26") (pin "29") (pinfunction "NC_29") (pintype "power_in+no_connect"))
    )
    (net (code "133") (name "unconnected-(IC26-NC-Pad30)") (class "Default")
      (node (ref "IC26") (pin "30") (pinfunction "NC_30") (pintype "power_in+no_connect"))
    )
    (net (code "134") (name "unconnected-(IC26-NC-Pad31)") (class "Default")
      (node (ref "IC26") (pin "31") (pinfunction "NC_31") (pintype "power_in+no_connect"))
    )
    (net (code "135") (name "unconnected-(IC26-P4_MDIN0-Pad18)") (class "Default")
      (node (ref "IC26") (pin "18") (pinfunction "P4_MDIN0_18") (pintype "bidirectional"))
    )
    (net (code "136") (name "unconnected-(IC26-P4_MDIN1-Pad21)") (class "Default")
      (node (ref "IC26") (pin "21") (pinfunction "P4_MDIN1_21") (pintype "bidirectional"))
    )
    (net (code "137") (name "unconnected-(IC26-P4_MDIN2-Pad24)") (class "Default")
      (node (ref "IC26") (pin "24") (pinfunction "P4_MDIN2_24") (pintype "bidirectional"))
    )
    (net (code "138") (name "unconnected-(IC26-P4_MDIN3-Pad26)") (class "Default")
      (node (ref "IC26") (pin "26") (pinfunction "P4_MDIN3_26") (pintype "bidirectional"))
    )
    (net (code "139") (name "unconnected-(IC26-P4_MDIP0-Pad17)") (class "Default")
      (node (ref "IC26") (pin "17") (pinfunction "P4_MDIP0_17") (pintype "bidirectional"))
    )
    (net (code "140") (name "unconnected-(IC26-P4_MDIP1-Pad20)") (class "Default")
      (node (ref "IC26") (pin "20") (pinfunction "P4_MDIP1_20") (pintype "bidirectional"))
    )
    (net (code "141") (name "unconnected-(IC26-P4_MDIP2-Pad23)") (class "Default")
      (node (ref "IC26") (pin "23") (pinfunction "P4_MDIP2_23") (pintype "bidirectional"))
    )
    (net (code "142") (name "unconnected-(IC26-P4_MDIP3-Pad25)") (class "Default")
      (node (ref "IC26") (pin "25") (pinfunction "P4_MDIP3_25") (pintype "bidirectional"))
    )
    (net (code "143") (name "unconnected-(IC26-SE_SCLK-Pad32)") (class "Default")
      (node (ref "IC26") (pin "32") (pinfunction "SE_SCLK_32") (pintype "input+no_connect"))
    )
    (net (code "144") (name "unconnected-(J7-Pad14)") (class "Default")
      (node (ref "J7") (pin "14") (pinfunction "14_14") (pintype "bidirectional"))
    )
    (net (code "145") (name "unconnected-(J7-Pad15)") (class "Default")
      (node (ref "J7") (pin "15") (pinfunction "15_15") (pintype "bidirectional"))
    )
    (net (code "146") (name "unconnected-(J7-Pad16)") (class "Default")
      (node (ref "J7") (pin "16") (pinfunction "16_16") (pintype "bidirectional"))
    )
  )
)
